# Sheet_1.net
KiCad netlist of a schematic drawn in Altium Designer
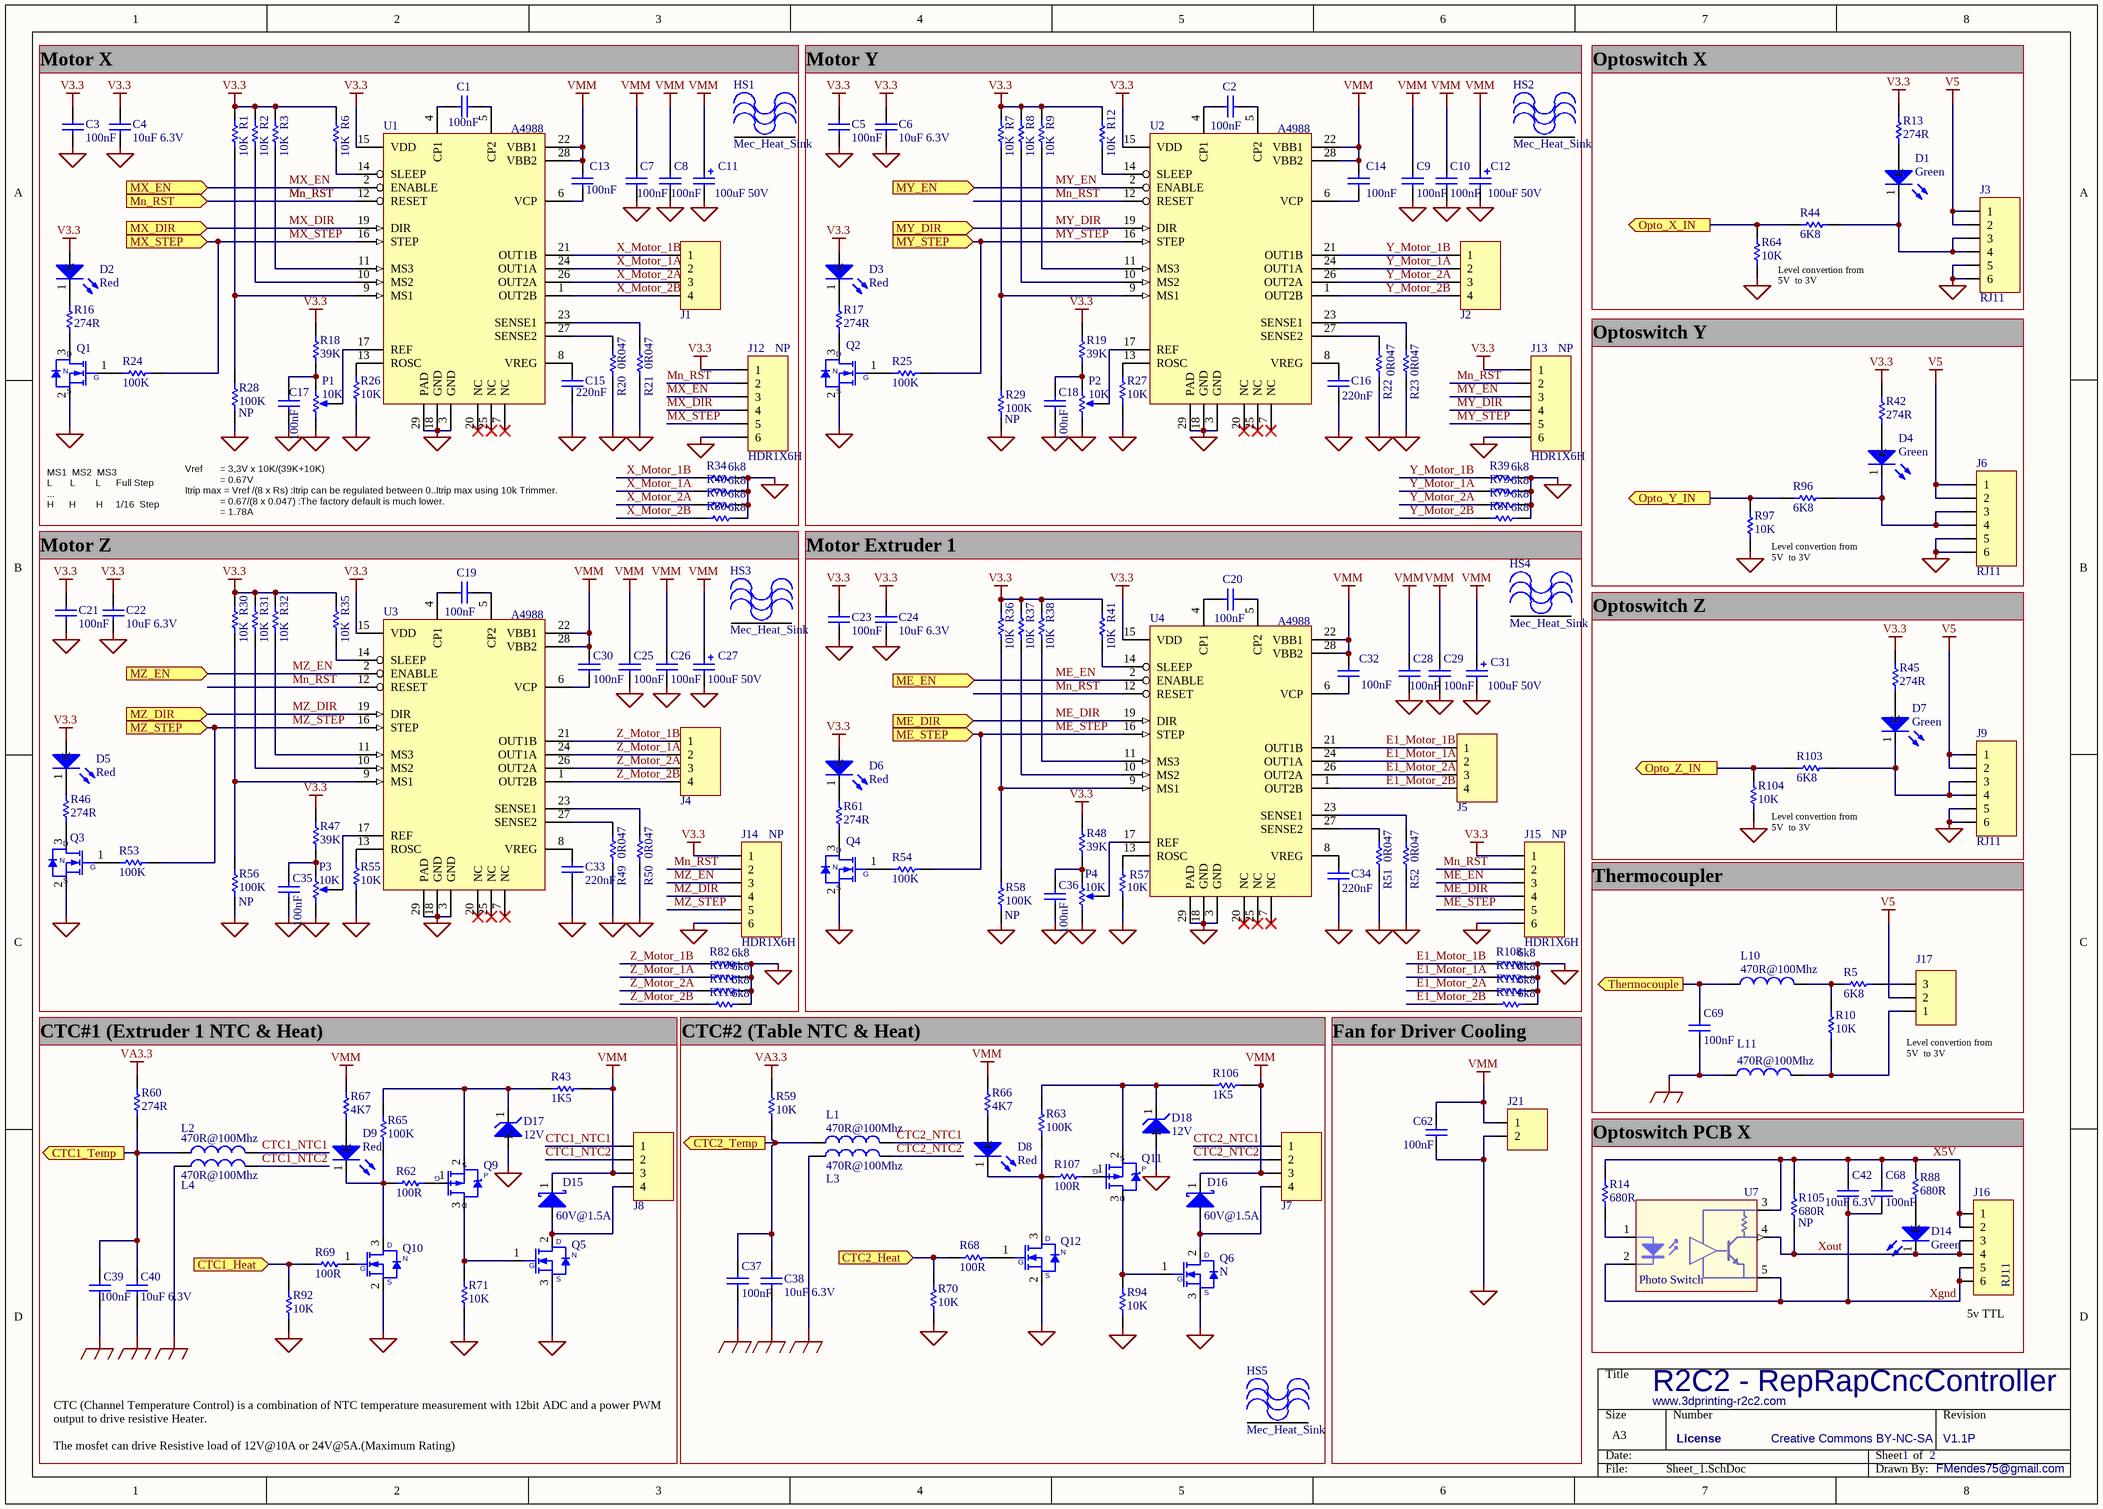
[diagram p0: Sheet_1.SchDoc]

(export (version "E")
  (design (tool "Eeschema 10.0.6"))
  (components
    (comp (ref "C1")
      (value "100nF")
      (footprint "CAPC1608M")
      (description "Capacitor - MLCC; 0603; NP0; 50V")
      (fields (field (name "PART NUMBER") "10000054") (field (name "MANUFACTURER") "Multicomp"))
      (libsource (lib "HB_DB_Components") (part "Cap Non Pol"))
    )
    (comp (ref "C2")
      (value "100nF")
      (footprint "CAPC1608M")
      (description "Capacitor Non Polarized")
      (fields (field (name "PART NUMBER") "10000054") (field (name "MANUFACTURER") "Multicomp"))
      (libsource (lib "HB_DB_Components") (part "Cap Non Pol"))
    )
    (comp (ref "C3")
      (value "100nF")
      (footprint "CAPC1608M")
      (description "Capacitor - MLCC; 0603; NP0; 50V")
      (fields (field (name "PART NUMBER") "10000054") (field (name "MANUFACTURER") "Multicomp"))
      (libsource (lib "HB_DB_Components") (part "Cap Non Pol"))
    )
    (comp (ref "C4")
      (value "10uF 6.3V")
      (footprint "CAPC2012M")
      (description "Capacitor - MLCC; 0805; Y5V; 10UF; 6.3V")
      (fields (field (name "PART NUMBER") "10000001") (field (name "MANUFACTURER") "MULTICOMP"))
      (libsource (lib "HB_DB_Components") (part "Cap Non Pol"))
    )
    (comp (ref "C5")
      (value "100nF")
      (footprint "CAPC1608M")
      (description "Capacitor - MLCC; 0603; NP0; 50V")
      (fields (field (name "PART NUMBER") "10000054") (field (name "MANUFACTURER") "Multicomp"))
      (libsource (lib "HB_DB_Components") (part "Cap Non Pol"))
    )
    (comp (ref "C6")
      (value "10uF 6.3V")
      (footprint "CAPC2012M")
      (description "Capacitor - MLCC; 0805; Y5V; 10UF; 6.3V")
      (fields (field (name "PART NUMBER") "10000001") (field (name "MANUFACTURER") "MULTICOMP"))
      (libsource (lib "HB_DB_Components") (part "Cap Non Pol"))
    )
    (comp (ref "C7")
      (value "100nF")
      (footprint "CAPC1608M")
      (description "Capacitor - MLCC; 0603; NP0; 50V")
      (fields (field (name "PART NUMBER") "10000054") (field (name "MANUFACTURER") "Multicomp"))
      (libsource (lib "HB_DB_Components") (part "Cap Non Pol"))
    )
    (comp (ref "C8")
      (value "100nF")
      (footprint "CAPC1608M")
      (description "Capacitor - MLCC; 0603; NP0; 50V")
      (fields (field (name "PART NUMBER") "10000054") (field (name "MANUFACTURER") "Multicomp"))
      (libsource (lib "HB_DB_Components") (part "Cap Non Pol"))
    )
    (comp (ref "C9")
      (value "100nF")
      (footprint "CAPC1608M")
      (description "Capacitor - MLCC; 0603; NP0; 50V")
      (fields (field (name "PART NUMBER") "10000054") (field (name "MANUFACTURER") "Multicomp"))
      (libsource (lib "HB_DB_Components") (part "Cap Non Pol"))
    )
    (comp (ref "C10")
      (value "100nF")
      (footprint "CAPC1608M")
      (description "Capacitor - MLCC; 0603; NP0; 50V")
      (fields (field (name "PART NUMBER") "10000054") (field (name "MANUFACTURER") "Multicomp"))
      (libsource (lib "HB_DB_Components") (part "Cap Non Pol"))
    )
    (comp (ref "C11")
      (value "100uF 50V")
      (footprint "CAPAE100X100M")
      (description "Capacitor - Al. Electrolytic; 100UF; 50V")
      (fields (field (name "PART NUMBER") "10000069") (field (name "MANUFACTURER") "Vishay"))
      (libsource (lib "HB_DB_Components") (part "Cap Pol"))
    )
    (comp (ref "C12")
      (value "100uF 50V")
      (footprint "CAPAE100X100M")
      (description "Capacitor - Al. Electrolytic; 100UF; 50V")
      (fields (field (name "PART NUMBER") "10000069") (field (name "MANUFACTURER") "Vishay"))
      (libsource (lib "HB_DB_Components") (part "Cap Pol"))
    )
    (comp (ref "C13")
      (value "100nF")
      (footprint "CAPC1608M")
      (description "Capacitor - MLCC; 0603; NP0; 50V")
      (fields (field (name "PART NUMBER") "10000054") (field (name "MANUFACTURER") "Multicomp"))
      (libsource (lib "HB_DB_Components") (part "Cap Non Pol"))
    )
    (comp (ref "C14")
      (value "100nF")
      (footprint "CAPC1608M")
      (description "Capacitor - MLCC; 0603; NP0; 50V")
      (fields (field (name "PART NUMBER") "10000054") (field (name "MANUFACTURER") "Multicomp"))
      (libsource (lib "HB_DB_Components") (part "Cap Non Pol"))
    )
    (comp (ref "C15")
      (value "220nF")
      (footprint "CAPC1608M")
      (description "Capacitor - MLCC; 0603; NP0; 50V")
      (fields (field (name "PART NUMBER") "10000059") (field (name "MANUFACTURER") "Multicomp"))
      (libsource (lib "HB_DB_Components") (part "Cap Non Pol"))
    )
    (comp (ref "C16")
      (value "220nF")
      (footprint "CAPC1608M")
      (description "Capacitor - MLCC; 0603; NP0; 50V")
      (fields (field (name "PART NUMBER") "10000059") (field (name "MANUFACTURER") "Multicomp"))
      (libsource (lib "HB_DB_Components") (part "Cap Non Pol"))
    )
    (comp (ref "C17")
      (value "100nF")
      (footprint "CAPC1608M")
      (description "Capacitor - MLCC; 0603; NP0; 50V")
      (fields (field (name "PART NUMBER") "10000054") (field (name "MANUFACTURER") "Multicomp"))
      (libsource (lib "HB_DB_Components") (part "Cap Non Pol"))
    )
    (comp (ref "C18")
      (value "100nF")
      (footprint "CAPC1608M")
      (description "Capacitor - MLCC; 0603; NP0; 50V")
      (fields (field (name "PART NUMBER") "10000054") (field (name "MANUFACTURER") "Multicomp"))
      (libsource (lib "HB_DB_Components") (part "Cap Non Pol"))
    )
    (comp (ref "C19")
      (value "100nF")
      (footprint "CAPC1608M")
      (description "Capacitor - MLCC; 0603; NP0; 50V")
      (fields (field (name "PART NUMBER") "10000054") (field (name "MANUFACTURER") "Multicomp"))
      (libsource (lib "HB_DB_Components") (part "Cap Non Pol"))
    )
    (comp (ref "C20")
      (value "100nF")
      (footprint "CAPC1608M")
      (description "Capacitor Non Polarized")
      (fields (field (name "PART NUMBER") "10000054") (field (name "MANUFACTURER") "Multicomp"))
      (libsource (lib "HB_DB_Components") (part "Cap Non Pol"))
    )
    (comp (ref "C21")
      (value "100nF")
      (footprint "CAPC1608M")
      (description "Capacitor - MLCC; 0603; NP0; 50V")
      (fields (field (name "PART NUMBER") "10000054") (field (name "MANUFACTURER") "Multicomp"))
      (libsource (lib "HB_DB_Components") (part "Cap Non Pol"))
    )
    (comp (ref "C22")
      (value "10uF 6.3V")
      (footprint "CAPC2012M")
      (description "Capacitor - MLCC; 0805; Y5V; 10UF; 6.3V")
      (fields (field (name "PART NUMBER") "10000001") (field (name "MANUFACTURER") "MULTICOMP"))
      (libsource (lib "HB_DB_Components") (part "Cap Non Pol"))
    )
    (comp (ref "C23")
      (value "100nF")
      (footprint "CAPC1608M")
      (description "Capacitor - MLCC; 0603; NP0; 50V")
      (fields (field (name "PART NUMBER") "10000054") (field (name "MANUFACTURER") "Multicomp"))
      (libsource (lib "HB_DB_Components") (part "Cap Non Pol"))
    )
    (comp (ref "C24")
      (value "10uF 6.3V")
      (footprint "CAPC2012M")
      (description "Capacitor - MLCC; 0805; Y5V; 10UF; 6.3V")
      (fields (field (name "PART NUMBER") "10000001") (field (name "MANUFACTURER") "MULTICOMP"))
      (libsource (lib "HB_DB_Components") (part "Cap Non Pol"))
    )
    (comp (ref "C25")
      (value "100nF")
      (footprint "CAPC1608M")
      (description "Capacitor - MLCC; 0603; NP0; 50V")
      (fields (field (name "PART NUMBER") "10000054") (field (name "MANUFACTURER") "Multicomp"))
      (libsource (lib "HB_DB_Components") (part "Cap Non Pol"))
    )
    (comp (ref "C26")
      (value "100nF")
      (footprint "CAPC1608M")
      (description "Capacitor - MLCC; 0603; NP0; 50V")
      (fields (field (name "PART NUMBER") "10000054") (field (name "MANUFACTURER") "Multicomp"))
      (libsource (lib "HB_DB_Components") (part "Cap Non Pol"))
    )
    (comp (ref "C27")
      (value "100uF 50V")
      (footprint "CAPAE100X100M")
      (description "Capacitor - Al. Electrolytic; 100UF; 50V")
      (fields (field (name "PART NUMBER") "10000069") (field (name "MANUFACTURER") "Vishay"))
      (libsource (lib "HB_DB_Components") (part "Cap Pol"))
    )
    (comp (ref "C28")
      (value "100nF")
      (footprint "CAPC1608M")
      (description "Capacitor - MLCC; 0603; NP0; 50V")
      (fields (field (name "PART NUMBER") "10000054") (field (name "MANUFACTURER") "Multicomp"))
      (libsource (lib "HB_DB_Components") (part "Cap Non Pol"))
    )
    (comp (ref "C29")
      (value "100nF")
      (footprint "CAPC1608M")
      (description "Capacitor - MLCC; 0603; NP0; 50V")
      (fields (field (name "PART NUMBER") "10000054") (field (name "MANUFACTURER") "Multicomp"))
      (libsource (lib "HB_DB_Components") (part "Cap Non Pol"))
    )
    (comp (ref "C30")
      (value "100nF")
      (footprint "CAPC1608M")
      (description "Capacitor - MLCC; 0603; NP0; 50V")
      (fields (field (name "PART NUMBER") "10000054") (field (name "MANUFACTURER") "Multicomp"))
      (libsource (lib "HB_DB_Components") (part "Cap Non Pol"))
    )
    (comp (ref "C31")
      (value "100uF 50V")
      (footprint "CAPAE100X100M")
      (description "Capacitor - Al. Electrolytic; 100UF; 50V")
      (fields (field (name "PART NUMBER") "10000069") (field (name "MANUFACTURER") "Vishay"))
      (libsource (lib "HB_DB_Components") (part "Cap Pol"))
    )
    (comp (ref "C32")
      (value "100nF")
      (footprint "CAPC1608M")
      (description "Capacitor - MLCC; 0603; NP0; 50V")
      (fields (field (name "PART NUMBER") "10000054") (field (name "MANUFACTURER") "Multicomp"))
      (libsource (lib "HB_DB_Components") (part "Cap Non Pol"))
    )
    (comp (ref "C33")
      (value "220nF")
      (footprint "CAPC1608M")
      (description "Capacitor - MLCC; 0603; NP0; 50V")
      (fields (field (name "PART NUMBER") "10000059") (field (name "MANUFACTURER") "Multicomp"))
      (libsource (lib "HB_DB_Components") (part "Cap Non Pol"))
    )
    (comp (ref "C34")
      (value "220nF")
      (footprint "CAPC1608M")
      (description "Capacitor - MLCC; 0603; NP0; 50V")
      (fields (field (name "PART NUMBER") "10000059") (field (name "MANUFACTURER") "Multicomp"))
      (libsource (lib "HB_DB_Components") (part "Cap Non Pol"))
    )
    (comp (ref "C35")
      (value "100nF")
      (footprint "CAPC1608M")
      (description "Capacitor - MLCC; 0603; NP0; 50V")
      (fields (field (name "PART NUMBER") "10000054") (field (name "MANUFACTURER") "Multicomp"))
      (libsource (lib "HB_DB_Components") (part "Cap Non Pol"))
    )
    (comp (ref "C36")
      (value "100nF")
      (footprint "CAPC1608M")
      (description "Capacitor - MLCC; 0603; NP0; 50V")
      (fields (field (name "PART NUMBER") "10000054") (field (name "MANUFACTURER") "Multicomp"))
      (libsource (lib "HB_DB_Components") (part "Cap Non Pol"))
    )
    (comp (ref "C37")
      (value "100nF")
      (footprint "CAPC1608M")
      (description "Capacitor - MLCC; 0603; NP0; 50V")
      (fields (field (name "PART NUMBER") "10000054") (field (name "MANUFACTURER") "Multicomp"))
      (libsource (lib "HB_DB_Components") (part "Cap Non Pol"))
    )
    (comp (ref "C38")
      (value "10uF 6.3V")
      (footprint "CAPC2012M")
      (description "Capacitor - MLCC; 0805; Y5V; 10UF; 6.3V")
      (fields (field (name "PART NUMBER") "10000001") (field (name "MANUFACTURER") "MULTICOMP"))
      (libsource (lib "HB_DB_Components") (part "Cap Non Pol"))
    )
    (comp (ref "C39")
      (value "100nF")
      (footprint "CAPC1608M")
      (description "Capacitor - MLCC; 0603; NP0; 50V")
      (fields (field (name "PART NUMBER") "10000054") (field (name "MANUFACTURER") "Multicomp"))
      (libsource (lib "HB_DB_Components") (part "Cap Non Pol"))
    )
    (comp (ref "C40")
      (value "10uF 6.3V")
      (footprint "CAPC2012M")
      (description "Capacitor - MLCC; 0805; Y5V; 10UF; 6.3V")
      (fields (field (name "PART NUMBER") "10000001") (field (name "MANUFACTURER") "MULTICOMP"))
      (libsource (lib "HB_DB_Components") (part "Cap Non Pol"))
    )
    (comp (ref "C42")
      (value "10uF 6.3V")
      (footprint "CAPC2012M")
      (description "Capacitor - MLCC; 0805; Y5V; 10UF; 6.3V")
      (fields (field (name "PART NUMBER") "10000001") (field (name "MANUFACTURER") "MULTICOMP"))
      (libsource (lib "HB_DB_Components") (part "Cap Non Pol"))
    )
    (comp (ref "C62")
      (value "100nF")
      (footprint "CAPC1608M")
      (description "Capacitor - MLCC; 0603; NP0; 50V")
      (fields (field (name "PART NUMBER") "10000054") (field (name "MANUFACTURER") "Multicomp"))
      (libsource (lib "HB_DB_Components") (part "Cap Non Pol"))
    )
    (comp (ref "C68")
      (value "100nF")
      (footprint "CAPC1608M")
      (description "Capacitor - MLCC; 0603; NP0; 50V")
      (fields (field (name "PART NUMBER") "10000054") (field (name "MANUFACTURER") "Multicomp"))
      (libsource (lib "HB_DB_Components") (part "Cap Non Pol"))
    )
    (comp (ref "C69")
      (value "100nF")
      (footprint "CAPC1608M")
      (description "Capacitor - MLCC; 0603; NP0; 50V")
      (fields (field (name "PART NUMBER") "10000054") (field (name "MANUFACTURER") "Multicomp"))
      (libsource (lib "HB_DB_Components") (part "Cap Non Pol"))
    )
    (comp (ref "D1")
      (value "Green")
      (footprint "LEDM_3216X12M")
      (description "Led - 1206; Green OSRAM")
      (fields (field (name "PART NUMBER") "10000008") (field (name "MANUFACTURER") "OSRAM"))
      (libsource (lib "HB_DB_Components") (part "LED"))
    )
    (comp (ref "D2")
      (value "Red")
      (footprint "LEDM_3216X12M")
      (description "Led - 1206; Red")
      (fields (field (name "PART NUMBER") "10000089"))
      (libsource (lib "HB_DB_Components") (part "LED"))
    )
    (comp (ref "D3")
      (value "Red")
      (footprint "LEDM_3216X12M")
      (description "Led - 1206; Red")
      (fields (field (name "PART NUMBER") "10000089"))
      (libsource (lib "HB_DB_Components") (part "LED"))
    )
    (comp (ref "D4")
      (value "Green")
      (footprint "LEDM_3216X12M")
      (description "Led - 1206; Green OSRAM")
      (fields (field (name "PART NUMBER") "10000008") (field (name "MANUFACTURER") "OSRAM"))
      (libsource (lib "HB_DB_Components") (part "LED"))
    )
    (comp (ref "D5")
      (value "Red")
      (footprint "LEDM_3216X12M")
      (description "Led - 1206; Red")
      (fields (field (name "PART NUMBER") "10000089"))
      (libsource (lib "HB_DB_Components") (part "LED"))
    )
    (comp (ref "D6")
      (value "Red")
      (footprint "LEDM_3216X12M")
      (description "Led - 1206; Red")
      (fields (field (name "PART NUMBER") "10000089"))
      (libsource (lib "HB_DB_Components") (part "LED"))
    )
    (comp (ref "D7")
      (value "Green")
      (footprint "LEDM_3216X12M")
      (description "Led - 1206; Green OSRAM")
      (fields (field (name "PART NUMBER") "10000008") (field (name "MANUFACTURER") "OSRAM"))
      (libsource (lib "HB_DB_Components") (part "LED"))
    )
    (comp (ref "D8")
      (value "Red")
      (footprint "LEDM_3216X12M")
      (description "Led - 1206; Red")
      (fields (field (name "PART NUMBER") "10000089"))
      (libsource (lib "HB_DB_Components") (part "LED"))
    )
    (comp (ref "D9")
      (value "Red")
      (footprint "LEDM_3216X12M")
      (description "Led - 1206; Red")
      (fields (field (name "PART NUMBER") "10000089"))
      (libsource (lib "HB_DB_Components") (part "LED"))
    )
    (comp (ref "D14")
      (value "Green")
      (footprint "LEDM_3216X12M")
      (description "Led - 1206; Green OSRAM")
      (fields (field (name "PART NUMBER") "10000008") (field (name "MANUFACTURER") "OSRAM"))
      (libsource (lib "HB_DB_Components") (part "LED"))
    )
    (comp (ref "D15")
      (value "60V@1.5A")
      (footprint "SMA")
      (description "Diode - Schottky; 1.5A; 60V")
      (fields (field (name "PART NUMBER") "10000010") (field (name "MANUFACTURER") "VISHAY"))
      (libsource (lib "HB_DB_Components") (part "D Schottky"))
    )
    (comp (ref "D16")
      (value "60V@1.5A")
      (footprint "SMA")
      (description "Diode - Schottky; 1.5A; 60V")
      (fields (field (name "PART NUMBER") "10000010") (field (name "MANUFACTURER") "VISHAY"))
      (libsource (lib "HB_DB_Components") (part "D Schottky"))
    )
    (comp (ref "D17")
      (value "12V")
      (footprint "SOD323")
      (description "Diode - Zener; 0.4W; 12V")
      (fields (field (name "PART NUMBER") "10000088") (field (name "MANUFACTURER") "NXP"))
      (libsource (lib "HB_DB_Components") (part "D Zener"))
    )
    (comp (ref "D18")
      (value "12V")
      (footprint "SOD323")
      (description "Diode - Zener; 0.4W; 12V")
      (fields (field (name "PART NUMBER") "10000088") (field (name "MANUFACTURER") "NXP"))
      (libsource (lib "HB_DB_Components") (part "D Zener"))
    )
    (comp (ref "HS1")
      (value "Mec_Heat_Sink")
      (footprint "HS_180x130x50")
      (description "Heat Sink - IC stiker")
      (fields (field (name "PART NUMBER") "10000090"))
      (libsource (lib "HB_DB_Components") (part "Mec_Heat_Sink"))
    )
    (comp (ref "HS2")
      (value "Mec_Heat_Sink")
      (footprint "HS_180x130x50")
      (description "Heat Sink - IC stiker")
      (fields (field (name "PART NUMBER") "10000090"))
      (libsource (lib "HB_DB_Components") (part "Mec_Heat_Sink"))
    )
    (comp (ref "HS3")
      (value "Mec_Heat_Sink")
      (footprint "HS_180x130x50")
      (description "Heat Sink - IC stiker")
      (fields (field (name "PART NUMBER") "10000090"))
      (libsource (lib "HB_DB_Components") (part "Mec_Heat_Sink"))
    )
    (comp (ref "HS4")
      (value "Mec_Heat_Sink")
      (footprint "HS_180x130x50")
      (description "Heat Sink - IC stiker")
      (fields (field (name "PART NUMBER") "10000090"))
      (libsource (lib "HB_DB_Components") (part "Mec_Heat_Sink"))
    )
    (comp (ref "HS5")
      (value "Mec_Heat_Sink")
      (footprint "FK_244_13_D2PAK")
      (description "Heat Sink - For D2PAK")
      (fields (field (name "PART NUMBER") "10000091") (field (name "MANUFACTURER") "Fischer Elektronik"))
      (libsource (lib "HB_DB_Components") (part "Mec_Heat_Sink"))
    )
    (comp (ref "J1")
      (value "Con 4")
      (footprint "WEIDMULLER_SL-5.08-04-90B")
      (description "Connector - Header male; Screw; 4way; Hor.")
      (fields (field (name "PART NUMBER") "10000023") (field (name "MANUFACTURER") "WEIDMULLER"))
      (libsource (lib "HB_DB_Components") (part "Con 4"))
    )
    (comp (ref "J2")
      (value "Con 4")
      (footprint "WEIDMULLER_SL-5.08-04-90B")
      (description "Connector - Header male; Screw; 4way; Hor.")
      (fields (field (name "PART NUMBER") "10000023") (field (name "MANUFACTURER") "WEIDMULLER"))
      (libsource (lib "HB_DB_Components") (part "Con 4"))
    )
    (comp (ref "J3")
      (value "RJ11")
      (footprint "MOLEX_95022-2667")
      (description "Connector - PCB; RJ11; 6/4 Low Profile; Hor.")
      (fields (field (name "PART NUMBER") "10000062") (field (name "MANUFACTURER") "Molex"))
      (libsource (lib "HB_DB_Components") (part "Con 6"))
    )
    (comp (ref "J4")
      (value "Con 4")
      (footprint "WEIDMULLER_SL-5.08-04-90B")
      (description "Connector - Header male; Screw; 4way; Hor.")
      (fields (field (name "PART NUMBER") "10000023") (field (name "MANUFACTURER") "WEIDMULLER"))
      (libsource (lib "HB_DB_Components") (part "Con 4"))
    )
    (comp (ref "J5")
      (value "Con 4")
      (footprint "WEIDMULLER_SL-5.08-04-90B")
      (description "Connector - Header male; Screw; 4way; Hor.")
      (fields (field (name "PART NUMBER") "10000023") (field (name "MANUFACTURER") "WEIDMULLER"))
      (libsource (lib "HB_DB_Components") (part "Con 4"))
    )
    (comp (ref "J6")
      (value "RJ11")
      (footprint "MOLEX_95022-2667")
      (description "Connector - PCB; RJ11; 6/4 Low Profile; Hor.")
      (fields (field (name "PART NUMBER") "10000062") (field (name "MANUFACTURER") "Molex"))
      (libsource (lib "HB_DB_Components") (part "Con 6"))
    )
    (comp (ref "J7")
      (value "Con 4")
      (footprint "WEIDMULLER_SL-5.08-04-90B")
      (description "Connector - Header male; Screw; 4way; Hor.")
      (fields (field (name "PART NUMBER") "10000023") (field (name "MANUFACTURER") "WEIDMULLER"))
      (libsource (lib "HB_DB_Components") (part "Con 4"))
    )
    (comp (ref "J8")
      (value "Con 4")
      (footprint "WEIDMULLER_SL-5.08-04-90B")
      (description "Connector - Header male; Screw; 4way; Hor.")
      (fields (field (name "PART NUMBER") "10000023") (field (name "MANUFACTURER") "WEIDMULLER"))
      (libsource (lib "HB_DB_Components") (part "Con 4"))
    )
    (comp (ref "J9")
      (value "RJ11")
      (footprint "MOLEX_95022-2667")
      (description "Connector - PCB; RJ11; 6/4 Low Profile; Hor.")
      (fields (field (name "PART NUMBER") "10000062") (field (name "MANUFACTURER") "Molex"))
      (libsource (lib "HB_DB_Components") (part "Con 6"))
    )
    (comp (ref "J12")
      (value "HDR1X6H")
      (footprint "HDR1X6")
      (description "Connector - Header 1x6; Vert..")
      (fields (field (name "PART NUMBER") "10000093") (field (name "POPULATE") "NP"))
      (libsource (lib "HB_DB_Components") (part "Con 6"))
    )
    (comp (ref "J13")
      (value "HDR1X6H")
      (footprint "HDR1X6")
      (description "Connector - Header 1x6; Vert..")
      (fields (field (name "PART NUMBER") "10000093") (field (name "POPULATE") "NP"))
      (libsource (lib "HB_DB_Components") (part "Con 6"))
    )
    (comp (ref "J14")
      (value "HDR1X6H")
      (footprint "HDR1X6")
      (description "Connector - Header 1x6; Vert..")
      (fields (field (name "PART NUMBER") "10000093") (field (name "POPULATE") "NP"))
      (libsource (lib "HB_DB_Components") (part "Con 6"))
    )
    (comp (ref "J15")
      (value "HDR1X6H")
      (footprint "HDR1X6")
      (description "Connector - Header 1x6; Vert..")
      (fields (field (name "PART NUMBER") "10000093") (field (name "POPULATE") "NP"))
      (libsource (lib "HB_DB_Components") (part "Con 6"))
    )
    (comp (ref "J16")
      (value "RJ11")
      (footprint "MOLEX_95022-2667")
      (description "Connector - PCB; RJ11; 6/4 Low Profile; Hor.")
      (fields (field (name "PART NUMBER") "10000062") (field (name "MANUFACTURER") "Molex"))
      (libsource (lib "HB_DB_Components") (part "Con 6"))
    )
    (comp (ref "J17")
      (value "Con 3")
      (footprint "phoenix-contact_smkdsn-5.08")
      (description "Terminal Block")
      (fields (field (name "PART NUMBER") "10000095") (field (name "MANUFACTURER") "Phoenix_Contact"))
      (libsource (lib "HB_DB_Components") (part "Con 3"))
    )
    (comp (ref "J21")
      (value "Con 2")
      (footprint "MOLEX_22-29-2021")
      (description "Connector - PCB; Header; SQ Pin, 2 way; 2.54mm; Vert")
      (fields (field (name "PART NUMBER") "10000097") (field (name "MANUFACTURER") "Molex"))
      (libsource (lib "HB_DB_Components") (part "Con 2"))
    )
    (comp (ref "L1")
      (value "470R@100Mhz")
      (footprint "INDC1608M")
      (description "Ferrite Bead - 470OHM; 0603")
      (fields (field (name "PART NUMBER") "10000032") (field (name "MANUFACTURER") "MURATA"))
      (libsource (lib "HB_DB_Components") (part "Ind"))
    )
    (comp (ref "L2")
      (value "470R@100Mhz")
      (footprint "INDC1608M")
      (description "Ferrite Bead - 470OHM; 0603")
      (fields (field (name "PART NUMBER") "10000032") (field (name "MANUFACTURER") "MURATA"))
      (libsource (lib "HB_DB_Components") (part "Ind"))
    )
    (comp (ref "L3")
      (value "470R@100Mhz")
      (footprint "INDC1608M")
      (description "Ferrite Bead - 470OHM; 0603")
      (fields (field (name "PART NUMBER") "10000032") (field (name "MANUFACTURER") "MURATA"))
      (libsource (lib "HB_DB_Components") (part "Ind"))
    )
    (comp (ref "L4")
      (value "470R@100Mhz")
      (footprint "INDC1608M")
      (description "Ferrite Bead - 470OHM; 0603")
      (fields (field (name "PART NUMBER") "10000032") (field (name "MANUFACTURER") "MURATA"))
      (libsource (lib "HB_DB_Components") (part "Ind"))
    )
    (comp (ref "L10")
      (value "470R@100Mhz")
      (footprint "INDC1608M")
      (description "Ferrite Bead - 470OHM; 0603")
      (fields (field (name "PART NUMBER") "10000032") (field (name "MANUFACTURER") "MURATA"))
      (libsource (lib "HB_DB_Components") (part "Ind"))
    )
    (comp (ref "L11")
      (value "470R@100Mhz")
      (footprint "INDC1608M")
      (description "Ferrite Bead - 470OHM; 0603")
      (fields (field (name "PART NUMBER") "10000032") (field (name "MANUFACTURER") "MURATA"))
      (libsource (lib "HB_DB_Components") (part "Ind"))
    )
    (comp (ref "P1")
      (value "10K")
      (footprint "Trimmer_14")
      (description "Resistor - Trimmer; 1/4\"; 10K")
      (fields (field (name "PART NUMBER") "10000092") (field (name "MANUFACTURER") "Bourns"))
      (libsource (lib "HB_DB_Components") (part "Res Pot"))
    )
    (comp (ref "P2")
      (value "10K")
      (footprint "Trimmer_14")
      (description "Resistor - Trimmer; 1/4\"; 10K")
      (fields (field (name "PART NUMBER") "10000092") (field (name "MANUFACTURER") "Bourns"))
      (libsource (lib "HB_DB_Components") (part "Res Pot"))
    )
    (comp (ref "P3")
      (value "10K")
      (footprint "Trimmer_14")
      (description "Resistor - Trimmer; 1/4\"; 10K")
      (fields (field (name "PART NUMBER") "10000092") (field (name "MANUFACTURER") "Bourns"))
      (libsource (lib "HB_DB_Components") (part "Res Pot"))
    )
    (comp (ref "P4")
      (value "10K")
      (footprint "Trimmer_14")
      (description "Resistor - Trimmer; 1/4\"; 10K")
      (fields (field (name "PART NUMBER") "10000092") (field (name "MANUFACTURER") "Bourns"))
      (libsource (lib "HB_DB_Components") (part "Res Pot"))
    )
    (comp (ref "Q1")
      (value "N")
      (footprint "SOT323-3AM")
      (description "Mosfet - N; 60V; 0.3A;")
      (fields (field (name "PART NUMBER") "10000039") (field (name "MANUFACTURER") "NXP"))
      (libsource (lib "HB_DB_Components") (part "Q MOSFET-N"))
    )
    (comp (ref "Q2")
      (value "N")
      (footprint "SOT323-3AM")
      (description "Mosfet - N; 60V; 0.3A;")
      (fields (field (name "PART NUMBER") "10000039") (field (name "MANUFACTURER") "NXP"))
      (libsource (lib "HB_DB_Components") (part "Q MOSFET-N"))
    )
    (comp (ref "Q3")
      (value "N")
      (footprint "SOT323-3AM")
      (description "Mosfet - N; 60V; 0.3A;")
      (fields (field (name "PART NUMBER") "10000039") (field (name "MANUFACTURER") "NXP"))
      (libsource (lib "HB_DB_Components") (part "Q MOSFET-N"))
    )
    (comp (ref "Q4")
      (value "N")
      (footprint "SOT323-3AM")
      (description "Mosfet - N; 60V; 0.3A;")
      (fields (field (name "PART NUMBER") "10000039") (field (name "MANUFACTURER") "NXP"))
      (libsource (lib "HB_DB_Components") (part "Q MOSFET-N"))
    )
    (comp (ref "Q5")
      (value "N")
      (footprint "D2PAK")
      (description "N-channel Enhancement Mode Field-effect Transistor (123/gds)")
      (fields (field (name "PART NUMBER") "10000078") (field (name "MANUFACTURER") "IR"))
      (libsource (lib "HB_DB_Components") (part "Q MOSFET-N_gds"))
    )
    (comp (ref "Q6")
      (value "N")
      (footprint "D2PAK")
      (description "N-channel Enhancement Mode Field-effect Transistor (123/gds)")
      (fields (field (name "PART NUMBER") "10000078") (field (name "MANUFACTURER") "IR"))
      (libsource (lib "HB_DB_Components") (part "Q MOSFET-N_gds"))
    )
    (comp (ref "Q9")
      (value "P")
      (footprint "SOT23-3M")
      (description "Mosfet - Power; Vdss=-30v; Rds=0.60; Id=-0.6A")
      (fields (field (name "PART NUMBER") "10000076") (field (name "MANUFACTURER") "IR"))
      (libsource (lib "HB_DB_Components") (part "MOS-P"))
    )
    (comp (ref "Q10")
      (value "N")
      (footprint "SOT323-3AM")
      (description "Mosfet - N; 60V; 0.3A;")
      (fields (field (name "PART NUMBER") "10000039") (field (name "MANUFACTURER") "NXP"))
      (libsource (lib "HB_DB_Components") (part "Q MOSFET-N"))
    )
    (comp (ref "Q11")
      (value "P")
      (footprint "SOT23-3M")
      (description "Mosfet - Power; Vdss=-30v; Rds=0.60; Id=-0.6A")
      (fields (field (name "PART NUMBER") "10000076") (field (name "MANUFACTURER") "IR"))
      (libsource (lib "HB_DB_Components") (part "MOS-P"))
    )
    (comp (ref "Q12")
      (value "N")
      (footprint "SOT323-3AM")
      (description "Mosfet - N; 60V; 0.3A;")
      (fields (field (name "PART NUMBER") "10000039") (field (name "MANUFACTURER") "NXP"))
      (libsource (lib "HB_DB_Components") (part "Q MOSFET-N"))
    )
    (comp (ref "R1")
      (value "10K")
      (footprint "RESC1608M")
      (description "Resistor - 0603; 0.063W; 1%")
      (fields (field (name "PART NUMBER") "10000044") (field (name "MANUFACTURER") "Multicomp"))
      (libsource (lib "HB_DB_Components") (part "Res"))
    )
    (comp (ref "R2")
      (value "10K")
      (footprint "RESC1608M")
      (description "Resistor - 0603; 0.063W; 1%")
      (fields (field (name "PART NUMBER") "10000044") (field (name "MANUFACTURER") "Multicomp"))
      (libsource (lib "HB_DB_Components") (part "Res"))
    )
    (comp (ref "R3")
      (value "10K")
      (footprint "RESC1608M")
      (description "Resistor - 0603; 0.063W; 1%")
      (fields (field (name "PART NUMBER") "10000044") (field (name "MANUFACTURER") "Multicomp"))
      (libsource (lib "HB_DB_Components") (part "Res"))
    )
    (comp (ref "R5")
      (value "6K8")
      (footprint "RESC1608M")
      (description "Resistor - 0603; 0.063W; 1%")
      (fields (field (name "PART NUMBER") "10000096"))
      (libsource (lib "HB_DB_Components") (part "Res"))
    )
    (comp (ref "R6")
      (value "10K")
      (footprint "RESC1608M")
      (description "Resistor - 0603; 0.063W; 1%")
      (fields (field (name "PART NUMBER") "10000044") (field (name "MANUFACTURER") "Multicomp"))
      (libsource (lib "HB_DB_Components") (part "Res"))
    )
    (comp (ref "R7")
      (value "10K")
      (footprint "RESC1608M")
      (description "Resistor - 0603; 0.063W; 1%")
      (fields (field (name "PART NUMBER") "10000044") (field (name "MANUFACTURER") "Multicomp"))
      (libsource (lib "HB_DB_Components") (part "Res"))
    )
    (comp (ref "R8")
      (value "10K")
      (footprint "RESC1608M")
      (description "Resistor - 0603; 0.063W; 1%")
      (fields (field (name "PART NUMBER") "10000044") (field (name "MANUFACTURER") "Multicomp"))
      (libsource (lib "HB_DB_Components") (part "Res"))
    )
    (comp (ref "R9")
      (value "10K")
      (footprint "RESC1608M")
      (description "Resistor - 0603; 0.063W; 1%")
      (fields (field (name "PART NUMBER") "10000044") (field (name "MANUFACTURER") "Multicomp"))
      (libsource (lib "HB_DB_Components") (part "Res"))
    )
    (comp (ref "R10")
      (value "10K")
      (footprint "RESC1608M")
      (description "Resistor")
      (fields (field (name "PART NUMBER") "10000044") (field (name "MANUFACTURER") "Multicomp"))
      (libsource (lib "HB_DB_Components") (part "Res"))
    )
    (comp (ref "R12")
      (value "10K")
      (footprint "RESC1608M")
      (description "Resistor - 0603; 0.063W; 1%")
      (fields (field (name "PART NUMBER") "10000044") (field (name "MANUFACTURER") "Multicomp"))
      (libsource (lib "HB_DB_Components") (part "Res"))
    )
    (comp (ref "R13")
      (value "274R")
      (footprint "RESC1608M")
      (description "Resistor - 0603; 0.063W; 1%")
      (fields (field (name "PART NUMBER") "10000041") (field (name "MANUFACTURER") "Multicomp"))
      (libsource (lib "HB_DB_Components") (part "Res"))
    )
    (comp (ref "R14")
      (value "680R")
      (footprint "RESC1608M")
      (description "Resistor - 0603; 0.063W; 1%")
      (fields (field (name "PART NUMBER") "10000061") (field (name "MANUFACTURER") "Multicomp"))
      (libsource (lib "HB_DB_Components") (part "Res"))
    )
    (comp (ref "R16")
      (value "274R")
      (footprint "RESC1608M")
      (description "Resistor - 0603; 0.063W; 1%")
      (fields (field (name "PART NUMBER") "10000041") (field (name "MANUFACTURER") "Multicomp"))
      (libsource (lib "HB_DB_Components") (part "Res"))
    )
    (comp (ref "R17")
      (value "274R")
      (footprint "RESC1608M")
      (description "Resistor - 0603; 0.063W; 1%")
      (fields (field (name "PART NUMBER") "10000041") (field (name "MANUFACTURER") "Multicomp"))
      (libsource (lib "HB_DB_Components") (part "Res"))
    )
    (comp (ref "R18")
      (value "39K")
      (footprint "RESC1608M")
      (description "Resistor - 0603; 0.063W; 1%")
      (fields (field (name "PART NUMBER") "10000087"))
      (libsource (lib "HB_DB_Components") (part "Res"))
    )
    (comp (ref "R19")
      (value "39K")
      (footprint "RESC1608M")
      (description "Resistor - 0603; 0.063W; 1%")
      (fields (field (name "PART NUMBER") "10000087"))
      (libsource (lib "HB_DB_Components") (part "Res"))
    )
    (comp (ref "R20")
      (value "0R047")
      (footprint "RESC3216M")
      (description "Resistor - 1206; 0.5W; 1%")
      (fields (field (name "PART NUMBER") "10000047") (field (name "MANUFACTURER") "YAGEO"))
      (libsource (lib "HB_DB_Components") (part "Res"))
    )
    (comp (ref "R21")
      (value "0R047")
      (footprint "RESC3216M")
      (description "Resistor - 1206; 0.5W; 1%")
      (fields (field (name "PART NUMBER") "10000047") (field (name "MANUFACTURER") "YAGEO"))
      (libsource (lib "HB_DB_Components") (part "Res"))
    )
    (comp (ref "R22")
      (value "0R047")
      (footprint "RESC3216M")
      (description "Resistor - 1206; 0.5W; 1%")
      (fields (field (name "PART NUMBER") "10000047") (field (name "MANUFACTURER") "YAGEO"))
      (libsource (lib "HB_DB_Components") (part "Res"))
    )
    (comp (ref "R23")
      (value "0R047")
      (footprint "RESC3216M")
      (description "Resistor - 1206; 0.5W; 1%")
      (fields (field (name "PART NUMBER") "10000047") (field (name "MANUFACTURER") "YAGEO"))
      (libsource (lib "HB_DB_Components") (part "Res"))
    )
    (comp (ref "R24")
      (value "100K")
      (footprint "RESC1608M")
      (description "Resistor - 0603; 0.063W; 1%")
      (fields (field (name "PART NUMBER") "10000045") (field (name "MANUFACTURER") "Multicomp"))
      (libsource (lib "HB_DB_Components") (part "Res"))
    )
    (comp (ref "R25")
      (value "100K")
      (footprint "RESC1608M")
      (description "Resistor - 0603; 0.063W; 1%")
      (fields (field (name "PART NUMBER") "10000045") (field (name "MANUFACTURER") "Multicomp"))
      (libsource (lib "HB_DB_Components") (part "Res"))
    )
    (comp (ref "R26")
      (value "10K")
      (footprint "RESC1608M")
      (description "Resistor - 0603; 0.063W; 1%")
      (fields (field (name "PART NUMBER") "10000044") (field (name "MANUFACTURER") "Multicomp"))
      (libsource (lib "HB_DB_Components") (part "Res"))
    )
    (comp (ref "R27")
      (value "10K")
      (footprint "RESC1608M")
      (description "Resistor - 0603; 0.063W; 1%")
      (fields (field (name "PART NUMBER") "10000044") (field (name "MANUFACTURER") "Multicomp"))
      (libsource (lib "HB_DB_Components") (part "Res"))
    )
    (comp (ref "R28")
      (value "100K")
      (footprint "RESC1608M")
      (description "Resistor - 0603; 0.063W; 1%")
      (fields
        (field (name "PART NUMBER") "10000045")
        (field (name "MANUFACTURER") "Multicomp")
        (field (name "POPULATE") "NP")
      )
      (libsource (lib "HB_DB_Components") (part "Res"))
    )
    (comp (ref "R29")
      (value "100K")
      (footprint "RESC1608M")
      (description "Resistor - 0603; 0.063W; 1%")
      (fields
        (field (name "PART NUMBER") "10000045")
        (field (name "MANUFACTURER") "Multicomp")
        (field (name "POPULATE") "NP")
      )
      (libsource (lib "HB_DB_Components") (part "Res"))
    )
    (comp (ref "R30")
      (value "10K")
      (footprint "RESC1608M")
      (description "Resistor - 0603; 0.063W; 1%")
      (fields (field (name "PART NUMBER") "10000044") (field (name "MANUFACTURER") "Multicomp"))
      (libsource (lib "HB_DB_Components") (part "Res"))
    )
    (comp (ref "R31")
      (value "10K")
      (footprint "RESC1608M")
      (description "Resistor - 0603; 0.063W; 1%")
      (fields (field (name "PART NUMBER") "10000044") (field (name "MANUFACTURER") "Multicomp"))
      (libsource (lib "HB_DB_Components") (part "Res"))
    )
    (comp (ref "R32")
      (value "10K")
      (footprint "RESC1608M")
      (description "Resistor - 0603; 0.063W; 1%")
      (fields (field (name "PART NUMBER") "10000044") (field (name "MANUFACTURER") "Multicomp"))
      (libsource (lib "HB_DB_Components") (part "Res"))
    )
    (comp (ref "R34")
      (value "6k8")
      (footprint "RESC2012L")
      (description "Resistor - 0805; 0.100W; 5%")
      (fields (field (name "PART NUMBER") "10000098"))
      (libsource (lib "HB_DB_Components") (part "Res"))
    )
    (comp (ref "R35")
      (value "10K")
      (footprint "RESC1608M")
      (description "Resistor - 0603; 0.063W; 1%")
      (fields (field (name "PART NUMBER") "10000044") (field (name "MANUFACTURER") "Multicomp"))
      (libsource (lib "HB_DB_Components") (part "Res"))
    )
    (comp (ref "R36")
      (value "10K")
      (footprint "RESC1608M")
      (description "Resistor - 0603; 0.063W; 1%")
      (fields (field (name "PART NUMBER") "10000044") (field (name "MANUFACTURER") "Multicomp"))
      (libsource (lib "HB_DB_Components") (part "Res"))
    )
    (comp (ref "R37")
      (value "10K")
      (footprint "RESC1608M")
      (description "Resistor - 0603; 0.063W; 1%")
      (fields (field (name "PART NUMBER") "10000044") (field (name "MANUFACTURER") "Multicomp"))
      (libsource (lib "HB_DB_Components") (part "Res"))
    )
    (comp (ref "R38")
      (value "10K")
      (footprint "RESC1608M")
      (description "Resistor - 0603; 0.063W; 1%")
      (fields (field (name "PART NUMBER") "10000044") (field (name "MANUFACTURER") "Multicomp"))
      (libsource (lib "HB_DB_Components") (part "Res"))
    )
    (comp (ref "R39")
      (value "6k8")
      (footprint "RESC2012L")
      (description "Resistor - 0805; 0.100W; 5%")
      (fields (field (name "PART NUMBER") "10000098"))
      (libsource (lib "HB_DB_Components") (part "Res"))
    )
    (comp (ref "R40")
      (value "6k8")
      (footprint "RESC2012L")
      (description "Resistor - 0805; 0.100W; 5%")
      (fields (field (name "PART NUMBER") "10000098"))
      (libsource (lib "HB_DB_Components") (part "Res"))
    )
    (comp (ref "R41")
      (value "10K")
      (footprint "RESC1608M")
      (description "Resistor - 0603; 0.063W; 1%")
      (fields (field (name "PART NUMBER") "10000044") (field (name "MANUFACTURER") "Multicomp"))
      (libsource (lib "HB_DB_Components") (part "Res"))
    )
    (comp (ref "R42")
      (value "274R")
      (footprint "RESC1608M")
      (description "Resistor - 0603; 0.063W; 1%")
      (fields (field (name "PART NUMBER") "10000041") (field (name "MANUFACTURER") "Multicomp"))
      (libsource (lib "HB_DB_Components") (part "Res"))
    )
    (comp (ref "R43")
      (value "1K5")
      (footprint "RESC1608M")
      (description "Resistor - 0603; 0.063W; 1%")
      (fields (field (name "PART NUMBER") "10000048") (field (name "MANUFACTURER") "Multicomp"))
      (libsource (lib "HB_DB_Components") (part "Res"))
    )
    (comp (ref "R44")
      (value "6K8")
      (footprint "RESC1608M")
      (description "Resistor - 0603; 0.063W; 1%")
      (fields (field (name "PART NUMBER") "10000096"))
      (libsource (lib "HB_DB_Components") (part "Res"))
    )
    (comp (ref "R45")
      (value "274R")
      (footprint "RESC1608M")
      (description "Resistor - 0603; 0.063W; 1%")
      (fields (field (name "PART NUMBER") "10000041") (field (name "MANUFACTURER") "Multicomp"))
      (libsource (lib "HB_DB_Components") (part "Res"))
    )
    (comp (ref "R46")
      (value "274R")
      (footprint "RESC1608M")
      (description "Resistor - 0603; 0.063W; 1%")
      (fields (field (name "PART NUMBER") "10000041") (field (name "MANUFACTURER") "Multicomp"))
      (libsource (lib "HB_DB_Components") (part "Res"))
    )
    (comp (ref "R47")
      (value "39K")
      (footprint "RESC1608M")
      (description "Resistor - 0603; 0.063W; 1%")
      (fields (field (name "PART NUMBER") "10000087"))
      (libsource (lib "HB_DB_Components") (part "Res"))
    )
    (comp (ref "R48")
      (value "39K")
      (footprint "RESC1608M")
      (description "Resistor - 0603; 0.063W; 1%")
      (fields (field (name "PART NUMBER") "10000087"))
      (libsource (lib "HB_DB_Components") (part "Res"))
    )
    (comp (ref "R49")
      (value "0R047")
      (footprint "RESC3216M")
      (description "Resistor - 1206; 0.5W; 1%")
      (fields (field (name "PART NUMBER") "10000047") (field (name "MANUFACTURER") "YAGEO"))
      (libsource (lib "HB_DB_Components") (part "Res"))
    )
    (comp (ref "R50")
      (value "0R047")
      (footprint "RESC3216M")
      (description "Resistor - 1206; 0.5W; 1%")
      (fields (field (name "PART NUMBER") "10000047") (field (name "MANUFACTURER") "YAGEO"))
      (libsource (lib "HB_DB_Components") (part "Res"))
    )
    (comp (ref "R51")
      (value "0R047")
      (footprint "RESC3216M")
      (description "Resistor - 1206; 0.5W; 1%")
      (fields (field (name "PART NUMBER") "10000047") (field (name "MANUFACTURER") "YAGEO"))
      (libsource (lib "HB_DB_Components") (part "Res"))
    )
    (comp (ref "R52")
      (value "0R047")
      (footprint "RESC3216M")
      (description "Resistor - 1206; 0.5W; 1%")
      (fields (field (name "PART NUMBER") "10000047") (field (name "MANUFACTURER") "YAGEO"))
      (libsource (lib "HB_DB_Components") (part "Res"))
    )
    (comp (ref "R53")
      (value "100K")
      (footprint "RESC1608M")
      (description "Resistor - 0603; 0.063W; 1%")
      (fields (field (name "PART NUMBER") "10000045") (field (name "MANUFACTURER") "Multicomp"))
      (libsource (lib "HB_DB_Components") (part "Res"))
    )
    (comp (ref "R54")
      (value "100K")
      (footprint "RESC1608M")
      (description "Resistor - 0603; 0.063W; 1%")
      (fields (field (name "PART NUMBER") "10000045") (field (name "MANUFACTURER") "Multicomp"))
      (libsource (lib "HB_DB_Components") (part "Res"))
    )
    (comp (ref "R55")
      (value "10K")
      (footprint "RESC1608M")
      (description "Resistor - 0603; 0.063W; 1%")
      (fields (field (name "PART NUMBER") "10000044") (field (name "MANUFACTURER") "Multicomp"))
      (libsource (lib "HB_DB_Components") (part "Res"))
    )
    (comp (ref "R56")
      (value "100K")
      (footprint "RESC1608M")
      (description "Resistor - 0603; 0.063W; 1%")
      (fields
        (field (name "PART NUMBER") "10000045")
        (field (name "MANUFACTURER") "Multicomp")
        (field (name "POPULATE") "NP")
      )
      (libsource (lib "HB_DB_Components") (part "Res"))
    )
    (comp (ref "R57")
      (value "10K")
      (footprint "RESC1608M")
      (description "Resistor - 0603; 0.063W; 1%")
      (fields (field (name "PART NUMBER") "10000044") (field (name "MANUFACTURER") "Multicomp"))
      (libsource (lib "HB_DB_Components") (part "Res"))
    )
    (comp (ref "R58")
      (value "100K")
      (footprint "RESC1608M")
      (description "Resistor - 0603; 0.063W; 1%")
      (fields
        (field (name "PART NUMBER") "10000045")
        (field (name "MANUFACTURER") "Multicomp")
        (field (name "POPULATE") "NP")
      )
      (libsource (lib "HB_DB_Components") (part "Res"))
    )
    (comp (ref "R59")
      (value "10K")
      (footprint "RESC1608M")
      (description "Resistor")
      (fields (field (name "PART NUMBER") "10000044") (field (name "MANUFACTURER") "Multicomp"))
      (libsource (lib "HB_DB_Components") (part "Res"))
    )
    (comp (ref "R60")
      (value "274R")
      (footprint "RESC1608M")
      (description "Resistor")
      (fields (field (name "PART NUMBER") "10000041") (field (name "MANUFACTURER") "Multicomp"))
      (libsource (lib "HB_DB_Components") (part "Res"))
    )
    (comp (ref "R61")
      (value "274R")
      (footprint "RESC1608M")
      (description "Resistor - 0603; 0.063W; 1%")
      (fields (field (name "PART NUMBER") "10000041") (field (name "MANUFACTURER") "Multicomp"))
      (libsource (lib "HB_DB_Components") (part "Res"))
    )
    (comp (ref "R62")
      (value "100R")
      (footprint "RESC1608M")
      (description "Resistor - 0603; 0.063W; 1%")
      (fields (field (name "PART NUMBER") "10000042") (field (name "MANUFACTURER") "Multicomp"))
      (libsource (lib "HB_DB_Components") (part "Res"))
    )
    (comp (ref "R63")
      (value "100K")
      (footprint "RESC1608M")
      (description "Resistor - 0603; 0.063W; 1%")
      (fields (field (name "PART NUMBER") "10000045") (field (name "MANUFACTURER") "Multicomp"))
      (libsource (lib "HB_DB_Components") (part "Res"))
    )
    (comp (ref "R64")
      (value "10K")
      (footprint "RESC1608M")
      (description "Resistor - 0603; 0.063W; 1%")
      (fields (field (name "PART NUMBER") "10000044") (field (name "MANUFACTURER") "Multicomp"))
      (libsource (lib "HB_DB_Components") (part "Res"))
    )
    (comp (ref "R65")
      (value "100K")
      (footprint "RESC1608M")
      (description "Resistor - 0603; 0.063W; 1%")
      (fields (field (name "PART NUMBER") "10000045") (field (name "MANUFACTURER") "Multicomp"))
      (libsource (lib "HB_DB_Components") (part "Res"))
    )
    (comp (ref "R66")
      (value "4K7")
      (footprint "RESC1608M")
      (description "Resistor - 0603; 0.063W; 1%")
      (fields (field (name "PART NUMBER") "10000050") (field (name "MANUFACTURER") "Multicomp"))
      (libsource (lib "HB_DB_Components") (part "Res"))
    )
    (comp (ref "R67")
      (value "4K7")
      (footprint "RESC1608M")
      (description "Resistor - 0603; 0.063W; 1%")
      (fields (field (name "PART NUMBER") "10000050") (field (name "MANUFACTURER") "Multicomp"))
      (libsource (lib "HB_DB_Components") (part "Res"))
    )
    (comp (ref "R68")
      (value "100R")
      (footprint "RESC1608M")
      (description "Resistor - 0603; 0.063W; 1%")
      (fields (field (name "PART NUMBER") "10000042") (field (name "MANUFACTURER") "Multicomp"))
      (libsource (lib "HB_DB_Components") (part "Res"))
    )
    (comp (ref "R69")
      (value "100R")
      (footprint "RESC1608M")
      (description "Resistor - 0603; 0.063W; 1%")
      (fields (field (name "PART NUMBER") "10000042") (field (name "MANUFACTURER") "Multicomp"))
      (libsource (lib "HB_DB_Components") (part "Res"))
    )
    (comp (ref "R70")
      (value "10K")
      (footprint "RESC1608M")
      (description "Resistor - 0603; 0.063W; 1%")
      (fields (field (name "PART NUMBER") "10000044") (field (name "MANUFACTURER") "Multicomp"))
      (libsource (lib "HB_DB_Components") (part "Res"))
    )
    (comp (ref "R71")
      (value "10K")
      (footprint "RESC1608M")
      (description "Resistor - 0603; 0.063W; 1%")
      (fields (field (name "PART NUMBER") "10000044") (field (name "MANUFACTURER") "Multicomp"))
      (libsource (lib "HB_DB_Components") (part "Res"))
    )
    (comp (ref "R73")
      (value "6k8")
      (footprint "RESC2012L")
      (description "Resistor - 0805; 0.100W; 5%")
      (fields (field (name "PART NUMBER") "10000098"))
      (libsource (lib "HB_DB_Components") (part "Res"))
    )
    (comp (ref "R78")
      (value "6k8")
      (footprint "RESC2012L")
      (description "Resistor - 0805; 0.100W; 5%")
      (fields (field (name "PART NUMBER") "10000098"))
      (libsource (lib "HB_DB_Components") (part "Res"))
    )
    (comp (ref "R79")
      (value "6k8")
      (footprint "RESC2012L")
      (description "Resistor - 0805; 0.100W; 5%")
      (fields (field (name "PART NUMBER") "10000098"))
      (libsource (lib "HB_DB_Components") (part "Res"))
    )
    (comp (ref "R80")
      (value "6k8")
      (footprint "RESC2012L")
      (description "Resistor - 0805; 0.100W; 5%")
      (fields (field (name "PART NUMBER") "10000098"))
      (libsource (lib "HB_DB_Components") (part "Res"))
    )
    (comp (ref "R81")
      (value "6k8")
      (footprint "RESC2012L")
      (description "Resistor - 0805; 0.100W; 5%")
      (fields (field (name "PART NUMBER") "10000098"))
      (libsource (lib "HB_DB_Components") (part "Res"))
    )
    (comp (ref "R82")
      (value "6k8")
      (footprint "RESC2012L")
      (description "Resistor - 0805; 0.100W; 5%")
      (fields (field (name "PART NUMBER") "10000098"))
      (libsource (lib "HB_DB_Components") (part "Res"))
    )
    (comp (ref "R88")
      (value "680R")
      (footprint "RESC1608M")
      (description "Resistor - 0603; 0.063W; 1%")
      (fields (field (name "PART NUMBER") "10000061") (field (name "MANUFACTURER") "Multicomp"))
      (libsource (lib "HB_DB_Components") (part "Res"))
    )
    (comp (ref "R92")
      (value "10K")
      (footprint "RESC1608M")
      (description "Resistor - 0603; 0.063W; 1%")
      (fields (field (name "PART NUMBER") "10000044") (field (name "MANUFACTURER") "Multicomp"))
      (libsource (lib "HB_DB_Components") (part "Res"))
    )
    (comp (ref "R94")
      (value "10K")
      (footprint "RESC1608M")
      (description "Resistor - 0603; 0.063W; 1%")
      (fields (field (name "PART NUMBER") "10000044") (field (name "MANUFACTURER") "Multicomp"))
      (libsource (lib "HB_DB_Components") (part "Res"))
    )
    (comp (ref "R96")
      (value "6K8")
      (footprint "RESC1608M")
      (description "Resistor - 0603; 0.063W; 1%")
      (fields (field (name "PART NUMBER") "10000096"))
      (libsource (lib "HB_DB_Components") (part "Res"))
    )
    (comp (ref "R97")
      (value "10K")
      (footprint "RESC1608M")
      (description "Resistor - 0603; 0.063W; 1%")
      (fields (field (name "PART NUMBER") "10000044") (field (name "MANUFACTURER") "Multicomp"))
      (libsource (lib "HB_DB_Components") (part "Res"))
    )
    (comp (ref "R103")
      (value "6K8")
      (footprint "RESC1608M")
      (description "Resistor - 0603; 0.063W; 1%")
      (fields (field (name "PART NUMBER") "10000096"))
      (libsource (lib "HB_DB_Components") (part "Res"))
    )
    (comp (ref "R104")
      (value "10K")
      (footprint "RESC1608M")
      (description "Resistor - 0603; 0.063W; 1%")
      (fields (field (name "PART NUMBER") "10000044") (field (name "MANUFACTURER") "Multicomp"))
      (libsource (lib "HB_DB_Components") (part "Res"))
    )
    (comp (ref "R105")
      (value "680R")
      (footprint "RESC1608M")
      (description "Resistor - 0603; 0.063W; 1%")
      (fields
        (field (name "PART NUMBER") "10000061")
        (field (name "MANUFACTURER") "Multicomp")
        (field (name "POPULATE") "NP")
      )
      (libsource (lib "HB_DB_Components") (part "Res"))
    )
    (comp (ref "R106")
      (value "1K5")
      (footprint "RESC1608M")
      (description "Resistor - 0603; 0.063W; 1%")
      (fields (field (name "PART NUMBER") "10000048") (field (name "MANUFACTURER") "Multicomp"))
      (libsource (lib "HB_DB_Components") (part "Res"))
    )
    (comp (ref "R107")
      (value "100R")
      (footprint "RESC1608M")
      (description "Resistor - 0603; 0.063W; 1%")
      (fields (field (name "PART NUMBER") "10000042") (field (name "MANUFACTURER") "Multicomp"))
      (libsource (lib "HB_DB_Components") (part "Res"))
    )
    (comp (ref "R108")
      (value "6k8")
      (footprint "RESC2012L")
      (description "Resistor - 0805; 0.100W; 5%")
      (fields (field (name "PART NUMBER") "10000098"))
      (libsource (lib "HB_DB_Components") (part "Res"))
    )
    (comp (ref "R109")
      (value "6k8")
      (footprint "RESC2012L")
      (description "Resistor - 0805; 0.100W; 5%")
      (fields (field (name "PART NUMBER") "10000098"))
      (libsource (lib "HB_DB_Components") (part "Res"))
    )
    (comp (ref "R110")
      (value "6k8")
      (footprint "RESC2012L")
      (description "Resistor - 0805; 0.100W; 5%")
      (fields (field (name "PART NUMBER") "10000098"))
      (libsource (lib "HB_DB_Components") (part "Res"))
    )
    (comp (ref "R111")
      (value "6k8")
      (footprint "RESC2012L")
      (description "Resistor - 0805; 0.100W; 5%")
      (fields (field (name "PART NUMBER") "10000098"))
      (libsource (lib "HB_DB_Components") (part "Res"))
    )
    (comp (ref "R112")
      (value "6k8")
      (footprint "RESC2012L")
      (description "Resistor - 0805; 0.100W; 5%")
      (fields (field (name "PART NUMBER") "10000098"))
      (libsource (lib "HB_DB_Components") (part "Res"))
    )
    (comp (ref "R113")
      (value "6k8")
      (footprint "RESC2012L")
      (description "Resistor - 0805; 0.100W; 5%")
      (fields (field (name "PART NUMBER") "10000098"))
      (libsource (lib "HB_DB_Components") (part "Res"))
    )
    (comp (ref "R114")
      (value "6k8")
      (footprint "RESC2012L")
      (description "Resistor - 0805; 0.100W; 5%")
      (fields (field (name "PART NUMBER") "10000098"))
      (libsource (lib "HB_DB_Components") (part "Res"))
    )
    (comp (ref "U1")
      (value "A4988")
      (footprint "QFN50P500X500X100-28M")
      (description "A4988 (A4983 pinout compatible)")
      (fields (field (name "PART NUMBER") "10000094") (field (name "MANUFACTURER") "Allegro"))
      (libsource (lib "HB_DB_Components") (part "IC A4988"))
    )
    (comp (ref "U2")
      (value "A4988")
      (footprint "QFN50P500X500X100-28M")
      (description "A4988 (A4983 pinout compatible)")
      (fields (field (name "PART NUMBER") "10000094") (field (name "MANUFACTURER") "Allegro"))
      (libsource (lib "HB_DB_Components") (part "IC A4988"))
    )
    (comp (ref "U3")
      (value "A4988")
      (footprint "QFN50P500X500X100-28M")
      (description "A4988 (A4983 pinout compatible)")
      (fields (field (name "PART NUMBER") "10000094") (field (name "MANUFACTURER") "Allegro"))
      (libsource (lib "HB_DB_Components") (part "IC A4988"))
    )
    (comp (ref "U4")
      (value "A4988")
      (footprint "QFN50P500X500X100-28M")
      (description "A4988 (A4983 pinout compatible)")
      (fields (field (name "PART NUMBER") "10000094") (field (name "MANUFACTURER") "Allegro"))
      (libsource (lib "HB_DB_Components") (part "IC A4988"))
    )
    (comp (ref "U7")
      (value "Photo Switch")
      (footprint "OPIC_122x50x10")
      (description "Opto - Switch; OPIC Sharp; Slotted 3mm; Vcc 5v")
      (fields (field (name "PART NUMBER") "10000075") (field (name "MANUFACTURER") "Sharp"))
      (libsource (lib "HB_DB_Components") (part "Photo_Switch"))
    )
  )
  (nets
    (net (code "1") (name "/CTC1_Heat") (class "Default")
      (node (ref "R69") (pin "1") (pinfunction "1_1") (pintype "passive"))
      (node (ref "R92") (pin "2") (pinfunction "2_2") (pintype "passive"))
    )
    (net (code "2") (name "/CTC1_NTC1") (class "Default")
      (node (ref "J8") (pin "1") (pinfunction "1_1") (pintype "passive"))
      (node (ref "L2") (pin "2") (pinfunction "2_2") (pintype "passive"))
    )
    (net (code "3") (name "/CTC1_NTC2") (class "Default")
      (node (ref "J8") (pin "2") (pinfunction "2_2") (pintype "passive"))
      (node (ref "L4") (pin "2") (pinfunction "2_2") (pintype "passive"))
    )
    (net (code "4") (name "/CTC1_Temp") (class "Default")
      (node (ref "C39") (pin "2") (pinfunction "2_2") (pintype "passive"))
      (node (ref "C40") (pin "2") (pinfunction "2_2") (pintype "passive"))
      (node (ref "L2") (pin "1") (pinfunction "1_1") (pintype "passive"))
      (node (ref "R60") (pin "1") (pinfunction "1_1") (pintype "passive"))
    )
    (net (code "5") (name "/CTC2_Heat") (class "Default")
      (node (ref "R68") (pin "1") (pinfunction "1_1") (pintype "passive"))
      (node (ref "R70") (pin "2") (pinfunction "2_2") (pintype "passive"))
    )
    (net (code "6") (name "/CTC2_NTC1") (class "Default")
      (node (ref "J7") (pin "1") (pinfunction "1_1") (pintype "passive"))
      (node (ref "L1") (pin "2") (pinfunction "2_2") (pintype "passive"))
    )
    (net (code "7") (name "/CTC2_NTC2") (class "Default")
      (node (ref "J7") (pin "2") (pinfunction "2_2") (pintype "passive"))
      (node (ref "L3") (pin "2") (pinfunction "2_2") (pintype "passive"))
    )
    (net (code "8") (name "/CTC2_Temp") (class "Default")
      (node (ref "C37") (pin "2") (pinfunction "2_2") (pintype "passive"))
      (node (ref "C38") (pin "2") (pinfunction "2_2") (pintype "passive"))
      (node (ref "L1") (pin "1") (pinfunction "1_1") (pintype "passive"))
      (node (ref "R59") (pin "1") (pinfunction "1_1") (pintype "passive"))
    )
    (net (code "9") (name "/E1_Motor_1A") (class "Default")
      (node (ref "J5") (pin "2") (pinfunction "2_2") (pintype "passive"))
      (node (ref "R110") (pin "1") (pinfunction "1_1") (pintype "passive"))
      (node (ref "U4") (pin "24") (pinfunction "OUT1A_24") (pintype "passive"))
    )
    (net (code "10") (name "/E1_Motor_1B") (class "Default")
      (node (ref "J5") (pin "1") (pinfunction "1_1") (pintype "passive"))
      (node (ref "R108") (pin "1") (pinfunction "1_1") (pintype "passive"))
      (node (ref "U4") (pin "21") (pinfunction "OUT1B_21") (pintype "passive"))
    )
    (net (code "11") (name "/E1_Motor_2A") (class "Default")
      (node (ref "J5") (pin "3") (pinfunction "3_3") (pintype "passive"))
      (node (ref "R112") (pin "1") (pinfunction "1_1") (pintype "passive"))
      (node (ref "U4") (pin "26") (pinfunction "OUT2A_26") (pintype "passive"))
    )
    (net (code "12") (name "/E1_Motor_2B") (class "Default")
      (node (ref "J5") (pin "4") (pinfunction "4_4") (pintype "passive"))
      (node (ref "R114") (pin "1") (pinfunction "1_1") (pintype "passive"))
      (node (ref "U4") (pin "1") (pinfunction "OUT2B_1") (pintype "passive"))
    )
    (net (code "13") (name "/ME_DIR") (class "Default")
      (node (ref "J15") (pin "4") (pinfunction "4_4") (pintype "passive"))
      (node (ref "U4") (pin "19") (pinfunction "DIR_19") (pintype "input"))
    )
    (net (code "14") (name "/ME_EN") (class "Default")
      (node (ref "J15") (pin "3") (pinfunction "3_3") (pintype "passive"))
      (node (ref "U4") (pin "2") (pinfunction "ENABLE_2") (pintype "passive"))
    )
    (net (code "15") (name "/ME_STEP") (class "Default")
      (node (ref "J15") (pin "5") (pinfunction "5_5") (pintype "passive"))
      (node (ref "R54") (pin "2") (pinfunction "2_2") (pintype "passive"))
      (node (ref "U4") (pin "16") (pinfunction "STEP_16") (pintype "input"))
    )
    (net (code "16") (name "/MX_DIR") (class "Default")
      (node (ref "J12") (pin "4") (pinfunction "4_4") (pintype "passive"))
      (node (ref "U1") (pin "19") (pinfunction "DIR_19") (pintype "input"))
    )
    (net (code "17") (name "/MX_EN") (class "Default")
      (node (ref "J12") (pin "3") (pinfunction "3_3") (pintype "passive"))
      (node (ref "U1") (pin "2") (pinfunction "ENABLE_2") (pintype "passive"))
    )
    (net (code "18") (name "/MX_STEP") (class "Default")
      (node (ref "J12") (pin "5") (pinfunction "5_5") (pintype "passive"))
      (node (ref "R24") (pin "2") (pinfunction "2_2") (pintype "passive"))
      (node (ref "U1") (pin "16") (pinfunction "STEP_16") (pintype "input"))
    )
    (net (code "19") (name "/MY_DIR") (class "Default")
      (node (ref "J13") (pin "4") (pinfunction "4_4") (pintype "passive"))
      (node (ref "U2") (pin "19") (pinfunction "DIR_19") (pintype "input"))
    )
    (net (code "20") (name "/MY_EN") (class "Default")
      (node (ref "J13") (pin "3") (pinfunction "3_3") (pintype "passive"))
      (node (ref "U2") (pin "2") (pinfunction "ENABLE_2") (pintype "passive"))
    )
    (net (code "21") (name "/MY_STEP") (class "Default")
      (node (ref "J13") (pin "5") (pinfunction "5_5") (pintype "passive"))
      (node (ref "R25") (pin "2") (pinfunction "2_2") (pintype "passive"))
      (node (ref "U2") (pin "16") (pinfunction "STEP_16") (pintype "input"))
    )
    (net (code "22") (name "/MZ_DIR") (class "Default")
      (node (ref "J14") (pin "4") (pinfunction "4_4") (pintype "passive"))
      (node (ref "U3") (pin "19") (pinfunction "DIR_19") (pintype "input"))
    )
    (net (code "23") (name "/MZ_EN") (class "Default")
      (node (ref "J14") (pin "3") (pinfunction "3_3") (pintype "passive"))
      (node (ref "U3") (pin "2") (pinfunction "ENABLE_2") (pintype "passive"))
    )
    (net (code "24") (name "/MZ_STEP") (class "Default")
      (node (ref "J14") (pin "5") (pinfunction "5_5") (pintype "passive"))
      (node (ref "R53") (pin "2") (pinfunction "2_2") (pintype "passive"))
      (node (ref "U3") (pin "16") (pinfunction "STEP_16") (pintype "input"))
    )
    (net (code "25") (name "/Mn_RST") (class "Default")
      (node (ref "J12") (pin "2") (pinfunction "2_2") (pintype "passive"))
      (node (ref "J13") (pin "2") (pinfunction "2_2") (pintype "passive"))
      (node (ref "J14") (pin "2") (pinfunction "2_2") (pintype "passive"))
      (node (ref "J15") (pin "2") (pinfunction "2_2") (pintype "passive"))
      (node (ref "U1") (pin "12") (pinfunction "RESET_12") (pintype "passive"))
      (node (ref "U2") (pin "12") (pinfunction "RESET_12") (pintype "passive"))
      (node (ref "U3") (pin "12") (pinfunction "RESET_12") (pintype "passive"))
      (node (ref "U4") (pin "12") (pinfunction "RESET_12") (pintype "passive"))
    )
    (net (code "26") (name "/Opto_X_IN") (class "Default")
      (node (ref "R44") (pin "2") (pinfunction "2_2") (pintype "passive"))
      (node (ref "R64") (pin "2") (pinfunction "2_2") (pintype "passive"))
    )
    (net (code "27") (name "/Opto_Y_IN") (class "Default")
      (node (ref "R96") (pin "2") (pinfunction "2_2") (pintype "passive"))
      (node (ref "R97") (pin "2") (pinfunction "2_2") (pintype "passive"))
    )
    (net (code "28") (name "/Opto_Z_IN") (class "Default")
      (node (ref "R103") (pin "2") (pinfunction "2_2") (pintype "passive"))
      (node (ref "R104") (pin "2") (pinfunction "2_2") (pintype "passive"))
    )
    (net (code "29") (name "/Thermocouple") (class "Default")
      (node (ref "C69") (pin "2") (pinfunction "2_2") (pintype "passive"))
      (node (ref "L10") (pin "1") (pinfunction "1_1") (pintype "passive"))
    )
    (net (code "30") (name "/X5V") (class "Default")
      (node (ref "C42") (pin "2") (pinfunction "2_2") (pintype "passive"))
      (node (ref "C68") (pin "2") (pinfunction "2_2") (pintype "passive"))
      (node (ref "J16") (pin "1") (pinfunction "1_1") (pintype "passive"))
      (node (ref "J16") (pin "2") (pinfunction "2_2") (pintype "passive"))
      (node (ref "R105") (pin "2") (pinfunction "2_2") (pintype "passive"))
      (node (ref "R14") (pin "2") (pinfunction "2_2") (pintype "passive"))
      (node (ref "R88") (pin "2") (pinfunction "2_2") (pintype "passive"))
      (node (ref "U7") (pin "3") (pinfunction "Vcc_3") (pintype "power_in"))
    )
    (net (code "31") (name "/X_Motor_1A") (class "Default")
      (node (ref "J1") (pin "2") (pinfunction "2_2") (pintype "passive"))
      (node (ref "R40") (pin "1") (pinfunction "1_1") (pintype "passive"))
      (node (ref "U1") (pin "24") (pinfunction "OUT1A_24") (pintype "passive"))
    )
    (net (code "32") (name "/X_Motor_1B") (class "Default")
      (node (ref "J1") (pin "1") (pinfunction "1_1") (pintype "passive"))
      (node (ref "R34") (pin "1") (pinfunction "1_1") (pintype "passive"))
      (node (ref "U1") (pin "21") (pinfunction "OUT1B_21") (pintype "passive"))
    )
    (net (code "33") (name "/X_Motor_2A") (class "Default")
      (node (ref "J1") (pin "3") (pinfunction "3_3") (pintype "passive"))
      (node (ref "R78") (pin "1") (pinfunction "1_1") (pintype "passive"))
      (node (ref "U1") (pin "26") (pinfunction "OUT2A_26") (pintype "passive"))
    )
    (net (code "34") (name "/X_Motor_2B") (class "Default")
      (node (ref "J1") (pin "4") (pinfunction "4_4") (pintype "passive"))
      (node (ref "R80") (pin "1") (pinfunction "1_1") (pintype "passive"))
      (node (ref "U1") (pin "1") (pinfunction "OUT2B_1") (pintype "passive"))
    )
    (net (code "35") (name "/Xgnd") (class "Default")
      (node (ref "C42") (pin "1") (pinfunction "1_1") (pintype "passive"))
      (node (ref "C68") (pin "1") (pinfunction "1_1") (pintype "passive"))
      (node (ref "J16") (pin "5") (pinfunction "5_5") (pintype "passive"))
      (node (ref "J16") (pin "6") (pinfunction "6_6") (pintype "passive"))
      (node (ref "U7") (pin "2") (pinfunction "K_2") (pintype "passive"))
      (node (ref "U7") (pin "5") (pinfunction "GND_5") (pintype "power_in"))
    )
    (net (code "36") (name "/Xout") (class "Default")
      (node (ref "D14") (pin "1") (pinfunction "K_1") (pintype "passive"))
      (node (ref "J16") (pin "3") (pinfunction "3_3") (pintype "passive"))
      (node (ref "J16") (pin "4") (pinfunction "4_4") (pintype "passive"))
      (node (ref "R105") (pin "1") (pinfunction "1_1") (pintype "passive"))
      (node (ref "U7") (pin "4") (pinfunction "Out_4") (pintype "output"))
    )
    (net (code "37") (name "/Y_Motor_1A") (class "Default")
      (node (ref "J2") (pin "2") (pinfunction "2_2") (pintype "passive"))
      (node (ref "R73") (pin "1") (pinfunction "1_1") (pintype "passive"))
      (node (ref "U2") (pin "24") (pinfunction "OUT1A_24") (pintype "passive"))
    )
    (net (code "38") (name "/Y_Motor_1B") (class "Default")
      (node (ref "J2") (pin "1") (pinfunction "1_1") (pintype "passive"))
      (node (ref "R39") (pin "1") (pinfunction "1_1") (pintype "passive"))
      (node (ref "U2") (pin "21") (pinfunction "OUT1B_21") (pintype "passive"))
    )
    (net (code "39") (name "/Y_Motor_2A") (class "Default")
      (node (ref "J2") (pin "3") (pinfunction "3_3") (pintype "passive"))
      (node (ref "R79") (pin "1") (pinfunction "1_1") (pintype "passive"))
      (node (ref "U2") (pin "26") (pinfunction "OUT2A_26") (pintype "passive"))
    )
    (net (code "40") (name "/Y_Motor_2B") (class "Default")
      (node (ref "J2") (pin "4") (pinfunction "4_4") (pintype "passive"))
      (node (ref "R81") (pin "1") (pinfunction "1_1") (pintype "passive"))
      (node (ref "U2") (pin "1") (pinfunction "OUT2B_1") (pintype "passive"))
    )
    (net (code "41") (name "/Z_Motor_1A") (class "Default")
      (node (ref "J4") (pin "2") (pinfunction "2_2") (pintype "passive"))
      (node (ref "R109") (pin "1") (pinfunction "1_1") (pintype "passive"))
      (node (ref "U3") (pin "24") (pinfunction "OUT1A_24") (pintype "passive"))
    )
    (net (code "42") (name "/Z_Motor_1B") (class "Default")
      (node (ref "J4") (pin "1") (pinfunction "1_1") (pintype "passive"))
      (node (ref "R82") (pin "1") (pinfunction "1_1") (pintype "passive"))
      (node (ref "U3") (pin "21") (pinfunction "OUT1B_21") (pintype "passive"))
    )
    (net (code "43") (name "/Z_Motor_2A") (class "Default")
      (node (ref "J4") (pin "3") (pinfunction "3_3") (pintype "passive"))
      (node (ref "R111") (pin "1") (pinfunction "1_1") (pintype "passive"))
      (node (ref "U3") (pin "26") (pinfunction "OUT2A_26") (pintype "passive"))
    )
    (net (code "44") (name "/Z_Motor_2B") (class "Default")
      (node (ref "J4") (pin "4") (pinfunction "4_4") (pintype "passive"))
      (node (ref "R113") (pin "1") (pinfunction "1_1") (pintype "passive"))
      (node (ref "U3") (pin "1") (pinfunction "OUT2B_1") (pintype "passive"))
    )
    (net (code "45") (name "GND") (class "Default")
      (node (ref "C10") (pin "1") (pinfunction "1_1") (pintype "passive"))
      (node (ref "C11") (pin "2") (pinfunction "2_2") (pintype "passive"))
      (node (ref "C12") (pin "2") (pinfunction "2_2") (pintype "passive"))
      (node (ref "C15") (pin "1") (pinfunction "1_1") (pintype "passive"))
      (node (ref "C16") (pin "1") (pinfunction "1_1") (pintype "passive"))
      (node (ref "C17") (pin "1") (pinfunction "1_1") (pintype "passive"))
      (node (ref "C18") (pin "2") (pinfunction "2_2") (pintype "passive"))
      (node (ref "C21") (pin "1") (pinfunction "1_1") (pintype "passive"))
      (node (ref "C22") (pin "1") (pinfunction "1_1") (pintype "passive"))
      (node (ref "C23") (pin "1") (pinfunction "1_1") (pintype "passive"))
      (node (ref "C24") (pin "1") (pinfunction "1_1") (pintype "passive"))
      (node (ref "C25") (pin "1") (pinfunction "1_1") (pintype "passive"))
      (node (ref "C26") (pin "1") (pinfunction "1_1") (pintype "passive"))
      (node (ref "C27") (pin "2") (pinfunction "2_2") (pintype "passive"))
      (node (ref "C28") (pin "1") (pinfunction "1_1") (pintype "passive"))
      (node (ref "C29") (pin "1") (pinfunction "1_1") (pintype "passive"))
      (node (ref "C3") (pin "1") (pinfunction "1_1") (pintype "passive"))
      (node (ref "C31") (pin "2") (pinfunction "2_2") (pintype "passive"))
      (node (ref "C33") (pin "1") (pinfunction "1_1") (pintype "passive"))
      (node (ref "C34") (pin "1") (pinfunction "1_1") (pintype "passive"))
      (node (ref "C35") (pin "1") (pinfunction "1_1") (pintype "passive"))
      (node (ref "C36") (pin "1") (pinfunction "1_1") (pintype "passive"))
      (node (ref "C4") (pin "1") (pinfunction "1_1") (pintype "passive"))
      (node (ref "C5") (pin "1") (pinfunction "1_1") (pintype "passive"))
      (node (ref "C6") (pin "1") (pinfunction "1_1") (pintype "passive"))
      (node (ref "C62") (pin "1") (pinfunction "1_1") (pintype "passive"))
      (node (ref "C7") (pin "2") (pinfunction "2_2") (pintype "passive"))
      (node (ref "C8") (pin "1") (pinfunction "1_1") (pintype "passive"))
      (node (ref "C9") (pin "1") (pinfunction "1_1") (pintype "passive"))
      (node (ref "D17") (pin "2") (pinfunction "A_2") (pintype "passive"))
      (node (ref "D18") (pin "2") (pinfunction "A_2") (pintype "passive"))
      (node (ref "J12") (pin "6") (pinfunction "6_6") (pintype "passive"))
      (node (ref "J13") (pin "6") (pinfunction "6_6") (pintype "passive"))
      (node (ref "J14") (pin "6") (pinfunction "6_6") (pintype "passive"))
      (node (ref "J15") (pin "6") (pinfunction "6_6") (pintype "passive"))
      (node (ref "J21") (pin "2") (pinfunction "2_2") (pintype "passive"))
      (node (ref "J3") (pin "5") (pinfunction "5_5") (pintype "passive"))
      (node (ref "J3") (pin "6") (pinfunction "6_6") (pintype "passive"))
      (node (ref "J6") (pin "5") (pinfunction "5_5") (pintype "passive"))
      (node (ref "J6") (pin "6") (pinfunction "6_6") (pintype "passive"))
      (node (ref "J9") (pin "5") (pinfunction "5_5") (pintype "passive"))
      (node (ref "J9") (pin "6") (pinfunction "6_6") (pintype "passive"))
      (node (ref "P1") (pin "1") (pinfunction "TOP_1") (pintype "passive"))
      (node (ref "P2") (pin "1") (pinfunction "TOP_1") (pintype "passive"))
      (node (ref "P3") (pin "1") (pinfunction "TOP_1") (pintype "passive"))
      (node (ref "P4") (pin "1") (pinfunction "TOP_1") (pintype "passive"))
      (node (ref "Q1") (pin "2") (pinfunction "S_2") (pintype "passive"))
      (node (ref "Q10") (pin "2") (pinfunction "S_2") (pintype "passive"))
      (node (ref "Q12") (pin "2") (pinfunction "S_2") (pintype "passive"))
      (node (ref "Q2") (pin "2") (pinfunction "S_2") (pintype "passive"))
      (node (ref "Q3") (pin "2") (pinfunction "S_2") (pintype "passive"))
      (node (ref "Q4") (pin "2") (pinfunction "S_2") (pintype "passive"))
      (node (ref "Q5") (pin "3") (pinfunction "S_3") (pintype "passive"))
      (node (ref "Q6") (pin "3") (pinfunction "S_3") (pintype "passive"))
      (node (ref "R104") (pin "1") (pinfunction "1_1") (pintype "passive"))
      (node (ref "R108") (pin "2") (pinfunction "2_2") (pintype "passive"))
      (node (ref "R109") (pin "2") (pinfunction "2_2") (pintype "passive"))
      (node (ref "R110") (pin "2") (pinfunction "2_2") (pintype "passive"))
      (node (ref "R111") (pin "2") (pinfunction "2_2") (pintype "passive"))
      (node (ref "R112") (pin "2") (pinfunction "2_2") (pintype "passive"))
      (node (ref "R113") (pin "2") (pinfunction "2_2") (pintype "passive"))
      (node (ref "R114") (pin "2") (pinfunction "2_2") (pintype "passive"))
      (node (ref "R20") (pin "1") (pinfunction "1_1") (pintype "passive"))
      (node (ref "R21") (pin "1") (pinfunction "1_1") (pintype "passive"))
      (node (ref "R22") (pin "1") (pinfunction "1_1") (pintype "passive"))
      (node (ref "R23") (pin "1") (pinfunction "1_1") (pintype "passive"))
      (node (ref "R26") (pin "1") (pinfunction "1_1") (pintype "passive"))
      (node (ref "R27") (pin "1") (pinfunction "1_1") (pintype "passive"))
      (node (ref "R28") (pin "1") (pinfunction "1_1") (pintype "passive"))
      (node (ref "R29") (pin "1") (pinfunction "1_1") (pintype "passive"))
      (node (ref "R34") (pin "2") (pinfunction "2_2") (pintype "passive"))
      (node (ref "R39") (pin "2") (pinfunction "2_2") (pintype "passive"))
      (node (ref "R40") (pin "2") (pinfunction "2_2") (pintype "passive"))
      (node (ref "R49") (pin "1") (pinfunction "1_1") (pintype "passive"))
      (node (ref "R50") (pin "1") (pinfunction "1_1") (pintype "passive"))
      (node (ref "R51") (pin "1") (pinfunction "1_1") (pintype "passive"))
      (node (ref "R52") (pin "1") (pinfunction "1_1") (pintype "passive"))
      (node (ref "R55") (pin "1") (pinfunction "1_1") (pintype "passive"))
      (node (ref "R56") (pin "1") (pinfunction "1_1") (pintype "passive"))
      (node (ref "R57") (pin "1") (pinfunction "1_1") (pintype "passive"))
      (node (ref "R58") (pin "1") (pinfunction "1_1") (pintype "passive"))
      (node (ref "R64") (pin "1") (pinfunction "1_1") (pintype "passive"))
      (node (ref "R70") (pin "1") (pinfunction "1_1") (pintype "passive"))
      (node (ref "R71") (pin "1") (pinfunction "1_1") (pintype "passive"))
      (node (ref "R73") (pin "2") (pinfunction "2_2") (pintype "passive"))
      (node (ref "R78") (pin "2") (pinfunction "2_2") (pintype "passive"))
      (node (ref "R79") (pin "2") (pinfunction "2_2") (pintype "passive"))
      (node (ref "R80") (pin "2") (pinfunction "2_2") (pintype "passive"))
      (node (ref "R81") (pin "2") (pinfunction "2_2") (pintype "passive"))
      (node (ref "R82") (pin "2") (pinfunction "2_2") (pintype "passive"))
      (node (ref "R92") (pin "1") (pinfunction "1_1") (pintype "passive"))
      (node (ref "R94") (pin "1") (pinfunction "1_1") (pintype "passive"))
      (node (ref "R97") (pin "1") (pinfunction "1_1") (pintype "passive"))
      (node (ref "U1") (pin "18") (pinfunction "GND_18") (pintype "passive"))
      (node (ref "U1") (pin "29") (pinfunction "PAD_29") (pintype "passive"))
      (node (ref "U1") (pin "3") (pinfunction "GND_3") (pintype "passive"))
      (node (ref "U2") (pin "18") (pinfunction "GND_18") (pintype "passive"))
      (node (ref "U2") (pin "29") (pinfunction "PAD_29") (pintype "passive"))
      (node (ref "U2") (pin "3") (pinfunction "GND_3") (pintype "passive"))
      (node (ref "U3") (pin "18") (pinfunction "GND_18") (pintype "passive"))
      (node (ref "U3") (pin "29") (pinfunction "PAD_29") (pintype "passive"))
      (node (ref "U3") (pin "3") (pinfunction "GND_3") (pintype "passive"))
      (node (ref "U4") (pin "18") (pinfunction "GND_18") (pintype "passive"))
      (node (ref "U4") (pin "29") (pinfunction "PAD_29") (pintype "passive"))
      (node (ref "U4") (pin "3") (pinfunction "GND_3") (pintype "passive"))
    )
    (net (code "46") (name "GND_A") (class "Default")
      (node (ref "C37") (pin "1") (pinfunction "1_1") (pintype "passive"))
      (node (ref "C38") (pin "1") (pinfunction "1_1") (pintype "passive"))
      (node (ref "C39") (pin "1") (pinfunction "1_1") (pintype "passive"))
      (node (ref "C40") (pin "1") (pinfunction "1_1") (pintype "passive"))
      (node (ref "C69") (pin "1") (pinfunction "1_1") (pintype "passive"))
      (node (ref "L11") (pin "1") (pinfunction "1_1") (pintype "passive"))
      (node (ref "L3") (pin "1") (pinfunction "1_1") (pintype "passive"))
      (node (ref "L4") (pin "1") (pinfunction "1_1") (pintype "passive"))
    )
    (net (code "47") (name "Net-(D1-A)") (class "Default")
      (node (ref "D1") (pin "2") (pinfunction "A_2") (pintype "passive"))
      (node (ref "R13") (pin "1") (pinfunction "1_1") (pintype "passive"))
    )
    (net (code "48") (name "Net-(D1-K)") (class "Default")
      (node (ref "D1") (pin "1") (pinfunction "K_1") (pintype "passive"))
      (node (ref "J3") (pin "3") (pinfunction "3_3") (pintype "passive"))
      (node (ref "J3") (pin "4") (pinfunction "4_4") (pintype "passive"))
      (node (ref "R44") (pin "1") (pinfunction "1_1") (pintype "passive"))
    )
    (net (code "49") (name "Net-(D2-K)") (class "Default")
      (node (ref "D2") (pin "1") (pinfunction "K_1") (pintype "passive"))
      (node (ref "R16") (pin "2") (pinfunction "2_2") (pintype "passive"))
    )
    (net (code "50") (name "Net-(D3-K)") (class "Default")
      (node (ref "D3") (pin "1") (pinfunction "K_1") (pintype "passive"))
      (node (ref "R17") (pin "2") (pinfunction "2_2") (pintype "passive"))
    )
    (net (code "51") (name "Net-(D4-A)") (class "Default")
      (node (ref "D4") (pin "2") (pinfunction "A_2") (pintype "passive"))
      (node (ref "R42") (pin "1") (pinfunction "1_1") (pintype "passive"))
    )
    (net (code "52") (name "Net-(D4-K)") (class "Default")
      (node (ref "D4") (pin "1") (pinfunction "K_1") (pintype "passive"))
      (node (ref "J6") (pin "3") (pinfunction "3_3") (pintype "passive"))
      (node (ref "J6") (pin "4") (pinfunction "4_4") (pintype "passive"))
      (node (ref "R96") (pin "1") (pinfunction "1_1") (pintype "passive"))
    )
    (net (code "53") (name "Net-(D5-K)") (class "Default")
      (node (ref "D5") (pin "1") (pinfunction "K_1") (pintype "passive"))
      (node (ref "R46") (pin "2") (pinfunction "2_2") (pintype "passive"))
    )
    (net (code "54") (name "Net-(D6-K)") (class "Default")
      (node (ref "D6") (pin "1") (pinfunction "K_1") (pintype "passive"))
      (node (ref "R61") (pin "2") (pinfunction "2_2") (pintype "passive"))
    )
    (net (code "55") (name "Net-(D7-A)") (class "Default")
      (node (ref "D7") (pin "2") (pinfunction "A_2") (pintype "passive"))
      (node (ref "R45") (pin "1") (pinfunction "1_1") (pintype "passive"))
    )
    (net (code "56") (name "Net-(D7-K)") (class "Default")
      (node (ref "D7") (pin "1") (pinfunction "K_1") (pintype "passive"))
      (node (ref "J9") (pin "3") (pinfunction "3_3") (pintype "passive"))
      (node (ref "J9") (pin "4") (pinfunction "4_4") (pintype "passive"))
      (node (ref "R103") (pin "1") (pinfunction "1_1") (pintype "passive"))
    )
    (net (code "57") (name "Net-(D8-A)") (class "Default")
      (node (ref "D8") (pin "2") (pinfunction "A_2") (pintype "passive"))
      (node (ref "R66") (pin "1") (pinfunction "1_1") (pintype "passive"))
    )
    (net (code "58") (name "Net-(D8-K)") (class "Default")
      (node (ref "D8") (pin "1") (pinfunction "K_1") (pintype "passive"))
      (node (ref "Q12") (pin "3") (pinfunction "D_3") (pintype "passive"))
      (node (ref "R107") (pin "1") (pinfunction "1_1") (pintype "passive"))
      (node (ref "R63") (pin "1") (pinfunction "1_1") (pintype "passive"))
    )
    (net (code "59") (name "Net-(D9-A)") (class "Default")
      (node (ref "D9") (pin "2") (pinfunction "A_2") (pintype "passive"))
      (node (ref "R67") (pin "1") (pinfunction "1_1") (pintype "passive"))
    )
    (net (code "60") (name "Net-(D9-K)") (class "Default")
      (node (ref "D9") (pin "1") (pinfunction "K_1") (pintype "passive"))
      (node (ref "Q10") (pin "3") (pinfunction "D_3") (pintype "passive"))
      (node (ref "R62") (pin "1") (pinfunction "1_1") (pintype "passive"))
      (node (ref "R65") (pin "1") (pinfunction "1_1") (pintype "passive"))
    )
    (net (code "61") (name "Net-(D14-A)") (class "Default")
      (node (ref "D14") (pin "2") (pinfunction "A_2") (pintype "passive"))
      (node (ref "R88") (pin "1") (pinfunction "1_1") (pintype "passive"))
    )
    (net (code "62") (name "Net-(D15-A)") (class "Default")
      (node (ref "D15") (pin "2") (pinfunction "A_2") (pintype "passive"))
      (node (ref "J8") (pin "4") (pinfunction "4_4") (pintype "passive"))
      (node (ref "Q5") (pin "2") (pinfunction "D_2") (pintype "passive"))
    )
    (net (code "63") (name "Net-(D16-A)") (class "Default")
      (node (ref "D16") (pin "2") (pinfunction "A_2") (pintype "passive"))
      (node (ref "J7") (pin "4") (pinfunction "4_4") (pintype "passive"))
      (node (ref "Q6") (pin "2") (pinfunction "D_2") (pintype "passive"))
    )
    (net (code "64") (name "Net-(D17-K)") (class "Default")
      (node (ref "D17") (pin "1") (pinfunction "K_1") (pintype "passive"))
      (node (ref "Q9") (pin "2") (pinfunction "S_2") (pintype "passive"))
      (node (ref "R43") (pin "1") (pinfunction "1_1") (pintype "passive"))
      (node (ref "R65") (pin "2") (pinfunction "2_2") (pintype "passive"))
    )
    (net (code "65") (name "Net-(D18-K)") (class "Default")
      (node (ref "D18") (pin "1") (pinfunction "K_1") (pintype "passive"))
      (node (ref "Q11") (pin "2") (pinfunction "S_2") (pintype "passive"))
      (node (ref "R106") (pin "1") (pinfunction "1_1") (pintype "passive"))
      (node (ref "R63") (pin "2") (pinfunction "2_2") (pintype "passive"))
    )
    (net (code "66") (name "Net-(J17-Pad1)") (class "Default")
      (node (ref "J17") (pin "1") (pinfunction "1_1") (pintype "passive"))
      (node (ref "L11") (pin "2") (pinfunction "2_2") (pintype "passive"))
      (node (ref "R10") (pin "2") (pinfunction "2_2") (pintype "passive"))
    )
    (net (code "67") (name "Net-(J17-Pad3)") (class "Default")
      (node (ref "J17") (pin "3") (pinfunction "3_3") (pintype "passive"))
      (node (ref "R5") (pin "2") (pinfunction "2_2") (pintype "passive"))
    )
    (net (code "68") (name "Net-(L10-Pad2)") (class "Default")
      (node (ref "L10") (pin "2") (pinfunction "2_2") (pintype "passive"))
      (node (ref "R10") (pin "1") (pinfunction "1_1") (pintype "passive"))
      (node (ref "R5") (pin "1") (pinfunction "1_1") (pintype "passive"))
    )
    (net (code "69") (name "Net-(P1-BOT)") (class "Default")
      (node (ref "C17") (pin "2") (pinfunction "2_2") (pintype "passive"))
      (node (ref "P1") (pin "2") (pinfunction "BOT_2") (pintype "passive"))
      (node (ref "R18") (pin "1") (pinfunction "1_1") (pintype "passive"))
    )
    (net (code "70") (name "Net-(P1-TAP)") (class "Default")
      (node (ref "P1") (pin "3") (pinfunction "TAP_3") (pintype "passive"))
      (node (ref "U1") (pin "17") (pinfunction "REF_17") (pintype "passive"))
    )
    (net (code "71") (name "Net-(P2-BOT)") (class "Default")
      (node (ref "C18") (pin "1") (pinfunction "1_1") (pintype "passive"))
      (node (ref "P2") (pin "2") (pinfunction "BOT_2") (pintype "passive"))
      (node (ref "R19") (pin "1") (pinfunction "1_1") (pintype "passive"))
    )
    (net (code "72") (name "Net-(P2-TAP)") (class "Default")
      (node (ref "P2") (pin "3") (pinfunction "TAP_3") (pintype "passive"))
      (node (ref "U2") (pin "17") (pinfunction "REF_17") (pintype "passive"))
    )
    (net (code "73") (name "Net-(P3-BOT)") (class "Default")
      (node (ref "C35") (pin "2") (pinfunction "2_2") (pintype "passive"))
      (node (ref "P3") (pin "2") (pinfunction "BOT_2") (pintype "passive"))
      (node (ref "R47") (pin "1") (pinfunction "1_1") (pintype "passive"))
    )
    (net (code "74") (name "Net-(P3-TAP)") (class "Default")
      (node (ref "P3") (pin "3") (pinfunction "TAP_3") (pintype "passive"))
      (node (ref "U3") (pin "17") (pinfunction "REF_17") (pintype "passive"))
    )
    (net (code "75") (name "Net-(P4-BOT)") (class "Default")
      (node (ref "C36") (pin "2") (pinfunction "2_2") (pintype "passive"))
      (node (ref "P4") (pin "2") (pinfunction "BOT_2") (pintype "passive"))
      (node (ref "R48") (pin "1") (pinfunction "1_1") (pintype "passive"))
    )
    (net (code "76") (name "Net-(P4-TAP)") (class "Default")
      (node (ref "P4") (pin "3") (pinfunction "TAP_3") (pintype "passive"))
      (node (ref "U4") (pin "17") (pinfunction "REF_17") (pintype "passive"))
    )
    (net (code "77") (name "Net-(Q1-D)") (class "Default")
      (node (ref "Q1") (pin "3") (pinfunction "D_3") (pintype "passive"))
      (node (ref "R16") (pin "1") (pinfunction "1_1") (pintype "passive"))
    )
    (net (code "78") (name "Net-(Q1-G)") (class "Default")
      (node (ref "Q1") (pin "1") (pinfunction "G_1") (pintype "passive"))
      (node (ref "R24") (pin "1") (pinfunction "1_1") (pintype "passive"))
    )
    (net (code "79") (name "Net-(Q2-D)") (class "Default")
      (node (ref "Q2") (pin "3") (pinfunction "D_3") (pintype "passive"))
      (node (ref "R17") (pin "1") (pinfunction "1_1") (pintype "passive"))
    )
    (net (code "80") (name "Net-(Q2-G)") (class "Default")
      (node (ref "Q2") (pin "1") (pinfunction "G_1") (pintype "passive"))
      (node (ref "R25") (pin "1") (pinfunction "1_1") (pintype "passive"))
    )
    (net (code "81") (name "Net-(Q3-D)") (class "Default")
      (node (ref "Q3") (pin "3") (pinfunction "D_3") (pintype "passive"))
      (node (ref "R46") (pin "1") (pinfunction "1_1") (pintype "passive"))
    )
    (net (code "82") (name "Net-(Q3-G)") (class "Default")
      (node (ref "Q3") (pin "1") (pinfunction "G_1") (pintype "passive"))
      (node (ref "R53") (pin "1") (pinfunction "1_1") (pintype "passive"))
    )
    (net (code "83") (name "Net-(Q4-D)") (class "Default")
      (node (ref "Q4") (pin "3") (pinfunction "D_3") (pintype "passive"))
      (node (ref "R61") (pin "1") (pinfunction "1_1") (pintype "passive"))
    )
    (net (code "84") (name "Net-(Q4-G)") (class "Default")
      (node (ref "Q4") (pin "1") (pinfunction "G_1") (pintype "passive"))
      (node (ref "R54") (pin "1") (pinfunction "1_1") (pintype "passive"))
    )
    (net (code "85") (name "Net-(Q5-G)") (class "Default")
      (node (ref "Q5") (pin "1") (pinfunction "G_1") (pintype "passive"))
      (node (ref "Q9") (pin "3") (pinfunction "D_3") (pintype "passive"))
      (node (ref "R71") (pin "2") (pinfunction "2_2") (pintype "passive"))
    )
    (net (code "86") (name "Net-(Q9-G)") (class "Default")
      (node (ref "Q9") (pin "1") (pinfunction "G_1") (pintype "passive"))
      (node (ref "R62") (pin "2") (pinfunction "2_2") (pintype "passive"))
    )
    (net (code "87") (name "Net-(Q10-G)") (class "Default")
      (node (ref "Q10") (pin "1") (pinfunction "G_1") (pintype "passive"))
      (node (ref "R69") (pin "2") (pinfunction "2_2") (pintype "passive"))
    )
    (net (code "88") (name "Net-(Q11-D)") (class "Default")
      (node (ref "Q11") (pin "3") (pinfunction "D_3") (pintype "passive"))
      (node (ref "Q6") (pin "1") (pinfunction "G_1") (pintype "passive"))
      (node (ref "R94") (pin "2") (pinfunction "2_2") (pintype "passive"))
    )
    (net (code "89") (name "Net-(Q11-G)") (class "Default")
      (node (ref "Q11") (pin "1") (pinfunction "G_1") (pintype "passive"))
      (node (ref "R107") (pin "2") (pinfunction "2_2") (pintype "passive"))
    )
    (net (code "90") (name "Net-(Q12-G)") (class "Default")
      (node (ref "Q12") (pin "1") (pinfunction "G_1") (pintype "passive"))
      (node (ref "R68") (pin "2") (pinfunction "2_2") (pintype "passive"))
    )
    (net (code "91") (name "Net-(U1-CP1)") (class "Default")
      (node (ref "C1") (pin "2") (pinfunction "2_2") (pintype "passive"))
      (node (ref "U1") (pin "4") (pinfunction "CP1_4") (pintype "passive"))
    )
    (net (code "92") (name "Net-(U1-CP2)") (class "Default")
      (node (ref "C1") (pin "1") (pinfunction "1_1") (pintype "passive"))
      (node (ref "U1") (pin "5") (pinfunction "CP2_5") (pintype "passive"))
    )
    (net (code "93") (name "Net-(U1-MS1)") (class "Default")
      (node (ref "R1") (pin "1") (pinfunction "1_1") (pintype "passive"))
      (node (ref "R28") (pin "2") (pinfunction "2_2") (pintype "passive"))
      (node (ref "U1") (pin "9") (pinfunction "MS1_9") (pintype "input"))
    )
    (net (code "94") (name "Net-(U1-MS2)") (class "Default")
      (node (ref "R2") (pin "1") (pinfunction "1_1") (pintype "passive"))
      (node (ref "U1") (pin "10") (pinfunction "MS2_10") (pintype "input"))
    )
    (net (code "95") (name "Net-(U1-MS3)") (class "Default")
      (node (ref "R3") (pin "1") (pinfunction "1_1") (pintype "passive"))
      (node (ref "U1") (pin "11") (pinfunction "MS3_11") (pintype "input"))
    )
    (net (code "96") (name "Net-(U1-ROSC)") (class "Default")
      (node (ref "R26") (pin "2") (pinfunction "2_2") (pintype "passive"))
      (node (ref "U1") (pin "13") (pinfunction "ROSC_13") (pintype "passive"))
    )
    (net (code "97") (name "Net-(U1-SENSE1)") (class "Default")
      (node (ref "R21") (pin "2") (pinfunction "2_2") (pintype "passive"))
      (node (ref "U1") (pin "23") (pinfunction "SENSE1_23") (pintype "passive"))
    )
    (net (code "98") (name "Net-(U1-SENSE2)") (class "Default")
      (node (ref "R20") (pin "2") (pinfunction "2_2") (pintype "passive"))
      (node (ref "U1") (pin "27") (pinfunction "SENSE2_27") (pintype "passive"))
    )
    (net (code "99") (name "Net-(U1-SLEEP)") (class "Default")
      (node (ref "R6") (pin "1") (pinfunction "1_1") (pintype "passive"))
      (node (ref "U1") (pin "14") (pinfunction "SLEEP_14") (pintype "passive"))
    )
    (net (code "100") (name "Net-(U1-VCP)") (class "Default")
      (node (ref "C13") (pin "1") (pinfunction "1_1") (pintype "passive"))
      (node (ref "U1") (pin "6") (pinfunction "VCP_6") (pintype "passive"))
    )
    (net (code "101") (name "Net-(U1-VREG)") (class "Default")
      (node (ref "C15") (pin "2") (pinfunction "2_2") (pintype "passive"))
      (node (ref "U1") (pin "8") (pinfunction "VREG_8") (pintype "passive"))
    )
    (net (code "102") (name "Net-(U2-CP1)") (class "Default")
      (node (ref "C2") (pin "1") (pinfunction "1_1") (pintype "passive"))
      (node (ref "U2") (pin "4") (pinfunction "CP1_4") (pintype "passive"))
    )
    (net (code "103") (name "Net-(U2-CP2)") (class "Default")
      (node (ref "C2") (pin "2") (pinfunction "2_2") (pintype "passive"))
      (node (ref "U2") (pin "5") (pinfunction "CP2_5") (pintype "passive"))
    )
    (net (code "104") (name "Net-(U2-MS1)") (class "Default")
      (node (ref "R29") (pin "2") (pinfunction "2_2") (pintype "passive"))
      (node (ref "R7") (pin "1") (pinfunction "1_1") (pintype "passive"))
      (node (ref "U2") (pin "9") (pinfunction "MS1_9") (pintype "input"))
    )
    (net (code "105") (name "Net-(U2-MS2)") (class "Default")
      (node (ref "R8") (pin "1") (pinfunction "1_1") (pintype "passive"))
      (node (ref "U2") (pin "10") (pinfunction "MS2_10") (pintype "input"))
    )
    (net (code "106") (name "Net-(U2-MS3)") (class "Default")
      (node (ref "R9") (pin "1") (pinfunction "1_1") (pintype "passive"))
      (node (ref "U2") (pin "11") (pinfunction "MS3_11") (pintype "input"))
    )
    (net (code "107") (name "Net-(U2-ROSC)") (class "Default")
      (node (ref "R27") (pin "2") (pinfunction "2_2") (pintype "passive"))
      (node (ref "U2") (pin "13") (pinfunction "ROSC_13") (pintype "passive"))
    )
    (net (code "108") (name "Net-(U2-SENSE1)") (class "Default")
      (node (ref "R23") (pin "2") (pinfunction "2_2") (pintype "passive"))
      (node (ref "U2") (pin "23") (pinfunction "SENSE1_23") (pintype "passive"))
    )
    (net (code "109") (name "Net-(U2-SENSE2)") (class "Default")
      (node (ref "R22") (pin "2") (pinfunction "2_2") (pintype "passive"))
      (node (ref "U2") (pin "27") (pinfunction "SENSE2_27") (pintype "passive"))
    )
    (net (code "110") (name "Net-(U2-SLEEP)") (class "Default")
      (node (ref "R12") (pin "1") (pinfunction "1_1") (pintype "passive"))
      (node (ref "U2") (pin "14") (pinfunction "SLEEP_14") (pintype "passive"))
    )
    (net (code "111") (name "Net-(U2-VCP)") (class "Default")
      (node (ref "C14") (pin "1") (pinfunction "1_1") (pintype "passive"))
      (node (ref "U2") (pin "6") (pinfunction "VCP_6") (pintype "passive"))
    )
    (net (code "112") (name "Net-(U2-VREG)") (class "Default")
      (node (ref "C16") (pin "2") (pinfunction "2_2") (pintype "passive"))
      (node (ref "U2") (pin "8") (pinfunction "VREG_8") (pintype "passive"))
    )
    (net (code "113") (name "Net-(U3-CP1)") (class "Default")
      (node (ref "C19") (pin "2") (pinfunction "2_2") (pintype "passive"))
      (node (ref "U3") (pin "4") (pinfunction "CP1_4") (pintype "passive"))
    )
    (net (code "114") (name "Net-(U3-CP2)") (class "Default")
      (node (ref "C19") (pin "1") (pinfunction "1_1") (pintype "passive"))
      (node (ref "U3") (pin "5") (pinfunction "CP2_5") (pintype "passive"))
    )
    (net (code "115") (name "Net-(U3-MS1)") (class "Default")
      (node (ref "R30") (pin "1") (pinfunction "1_1") (pintype "passive"))
      (node (ref "R56") (pin "2") (pinfunction "2_2") (pintype "passive"))
      (node (ref "U3") (pin "9") (pinfunction "MS1_9") (pintype "input"))
    )
    (net (code "116") (name "Net-(U3-MS2)") (class "Default")
      (node (ref "R31") (pin "1") (pinfunction "1_1") (pintype "passive"))
      (node (ref "U3") (pin "10") (pinfunction "MS2_10") (pintype "input"))
    )
    (net (code "117") (name "Net-(U3-MS3)") (class "Default")
      (node (ref "R32") (pin "1") (pinfunction "1_1") (pintype "passive"))
      (node (ref "U3") (pin "11") (pinfunction "MS3_11") (pintype "input"))
    )
    (net (code "118") (name "Net-(U3-ROSC)") (class "Default")
      (node (ref "R55") (pin "2") (pinfunction "2_2") (pintype "passive"))
      (node (ref "U3") (pin "13") (pinfunction "ROSC_13") (pintype "passive"))
    )
    (net (code "119") (name "Net-(U3-SENSE1)") (class "Default")
      (node (ref "R50") (pin "2") (pinfunction "2_2") (pintype "passive"))
      (node (ref "U3") (pin "23") (pinfunction "SENSE1_23") (pintype "passive"))
    )
    (net (code "120") (name "Net-(U3-SENSE2)") (class "Default")
      (node (ref "R49") (pin "2") (pinfunction "2_2") (pintype "passive"))
      (node (ref "U3") (pin "27") (pinfunction "SENSE2_27") (pintype "passive"))
    )
    (net (code "121") (name "Net-(U3-SLEEP)") (class "Default")
      (node (ref "R35") (pin "1") (pinfunction "1_1") (pintype "passive"))
      (node (ref "U3") (pin "14") (pinfunction "SLEEP_14") (pintype "passive"))
    )
    (net (code "122") (name "Net-(U3-VCP)") (class "Default")
      (node (ref "C30") (pin "1") (pinfunction "1_1") (pintype "passive"))
      (node (ref "U3") (pin "6") (pinfunction "VCP_6") (pintype "passive"))
    )
    (net (code "123") (name "Net-(U3-VREG)") (class "Default")
      (node (ref "C33") (pin "2") (pinfunction "2_2") (pintype "passive"))
      (node (ref "U3") (pin "8") (pinfunction "VREG_8") (pintype "passive"))
    )
    (net (code "124") (name "Net-(U4-CP1)") (class "Default")
      (node (ref "C20") (pin "1") (pinfunction "1_1") (pintype "passive"))
      (node (ref "U4") (pin "4") (pinfunction "CP1_4") (pintype "passive"))
    )
    (net (code "125") (name "Net-(U4-CP2)") (class "Default")
      (node (ref "C20") (pin "2") (pinfunction "2_2") (pintype "passive"))
      (node (ref "U4") (pin "5") (pinfunction "CP2_5") (pintype "passive"))
    )
    (net (code "126") (name "Net-(U4-MS1)") (class "Default")
      (node (ref "R36") (pin "1") (pinfunction "1_1") (pintype "passive"))
      (node (ref "R58") (pin "2") (pinfunction "2_2") (pintype "passive"))
      (node (ref "U4") (pin "9") (pinfunction "MS1_9") (pintype "input"))
    )
    (net (code "127") (name "Net-(U4-MS2)") (class "Default")
      (node (ref "R37") (pin "1") (pinfunction "1_1") (pintype "passive"))
      (node (ref "U4") (pin "10") (pinfunction "MS2_10") (pintype "input"))
    )
    (net (code "128") (name "Net-(U4-MS3)") (class "Default")
      (node (ref "R38") (pin "1") (pinfunction "1_1") (pintype "passive"))
      (node (ref "U4") (pin "11") (pinfunction "MS3_11") (pintype "input"))
    )
    (net (code "129") (name "Net-(U4-ROSC)") (class "Default")
      (node (ref "R57") (pin "2") (pinfunction "2_2") (pintype "passive"))
      (node (ref "U4") (pin "13") (pinfunction "ROSC_13") (pintype "passive"))
    )
    (net (code "130") (name "Net-(U4-SENSE1)") (class "Default")
      (node (ref "R52") (pin "2") (pinfunction "2_2") (pintype "passive"))
      (node (ref "U4") (pin "23") (pinfunction "SENSE1_23") (pintype "passive"))
    )
    (net (code "131") (name "Net-(U4-SENSE2)") (class "Default")
      (node (ref "R51") (pin "2") (pinfunction "2_2") (pintype "passive"))
      (node (ref "U4") (pin "27") (pinfunction "SENSE2_27") (pintype "passive"))
    )
    (net (code "132") (name "Net-(U4-SLEEP)") (class "Default")
      (node (ref "R41") (pin "1") (pinfunction "1_1") (pintype "passive"))
      (node (ref "U4") (pin "14") (pinfunction "SLEEP_14") (pintype "passive"))
    )
    (net (code "133") (name "Net-(U4-VCP)") (class "Default")
      (node (ref "C32") (pin "1") (pinfunction "1_1") (pintype "passive"))
      (node (ref "U4") (pin "6") (pinfunction "VCP_6") (pintype "passive"))
    )
    (net (code "134") (name "Net-(U4-VREG)") (class "Default")
      (node (ref "C34") (pin "2") (pinfunction "2_2") (pintype "passive"))
      (node (ref "U4") (pin "8") (pinfunction "VREG_8") (pintype "passive"))
    )
    (net (code "135") (name "Net-(U7-A)") (class "Default")
      (node (ref "R14") (pin "1") (pinfunction "1_1") (pintype "passive"))
      (node (ref "U7") (pin "1") (pinfunction "A_1") (pintype "passive"))
    )
    (net (code "136") (name "V3.3") (class "Default")
      (node (ref "C21") (pin "2") (pinfunction "2_2") (pintype "passive"))
      (node (ref "C22") (pin "2") (pinfunction "2_2") (pintype "passive"))
      (node (ref "C23") (pin "2") (pinfunction "2_2") (pintype "passive"))
      (node (ref "C24") (pin "2") (pinfunction "2_2") (pintype "passive"))
      (node (ref "C3") (pin "2") (pinfunction "2_2") (pintype "passive"))
      (node (ref "C4") (pin "2") (pinfunction "2_2") (pintype "passive"))
      (node (ref "C5") (pin "2") (pinfunction "2_2") (pintype "passive"))
      (node (ref "C6") (pin "2") (pinfunction "2_2") (pintype "passive"))
      (node (ref "D2") (pin "2") (pinfunction "A_2") (pintype "passive"))
      (node (ref "D3") (pin "2") (pinfunction "A_2") (pintype "passive"))
      (node (ref "D5") (pin "2") (pinfunction "A_2") (pintype "passive"))
      (node (ref "D6") (pin "2") (pinfunction "A_2") (pintype "passive"))
      (node (ref "J12") (pin "1") (pinfunction "1_1") (pintype "passive"))
      (node (ref "J13") (pin "1") (pinfunction "1_1") (pintype "passive"))
      (node (ref "J14") (pin "1") (pinfunction "1_1") (pintype "passive"))
      (node (ref "J15") (pin "1") (pinfunction "1_1") (pintype "passive"))
      (node (ref "R1") (pin "2") (pinfunction "2_2") (pintype "passive"))
      (node (ref "R12") (pin "2") (pinfunction "2_2") (pintype "passive"))
      (node (ref "R13") (pin "2") (pinfunction "2_2") (pintype "passive"))
      (node (ref "R18") (pin "2") (pinfunction "2_2") (pintype "passive"))
      (node (ref "R19") (pin "2") (pinfunction "2_2") (pintype "passive"))
      (node (ref "R2") (pin "2") (pinfunction "2_2") (pintype "passive"))
      (node (ref "R3") (pin "2") (pinfunction "2_2") (pintype "passive"))
      (node (ref "R30") (pin "2") (pinfunction "2_2") (pintype "passive"))
      (node (ref "R31") (pin "2") (pinfunction "2_2") (pintype "passive"))
      (node (ref "R32") (pin "2") (pinfunction "2_2") (pintype "passive"))
      (node (ref "R35") (pin "2") (pinfunction "2_2") (pintype "passive"))
      (node (ref "R36") (pin "2") (pinfunction "2_2") (pintype "passive"))
      (node (ref "R37") (pin "2") (pinfunction "2_2") (pintype "passive"))
      (node (ref "R38") (pin "2") (pinfunction "2_2") (pintype "passive"))
      (node (ref "R41") (pin "2") (pinfunction "2_2") (pintype "passive"))
      (node (ref "R42") (pin "2") (pinfunction "2_2") (pintype "passive"))
      (node (ref "R45") (pin "2") (pinfunction "2_2") (pintype "passive"))
      (node (ref "R47") (pin "2") (pinfunction "2_2") (pintype "passive"))
      (node (ref "R48") (pin "2") (pinfunction "2_2") (pintype "passive"))
      (node (ref "R6") (pin "2") (pinfunction "2_2") (pintype "passive"))
      (node (ref "R7") (pin "2") (pinfunction "2_2") (pintype "passive"))
      (node (ref "R8") (pin "2") (pinfunction "2_2") (pintype "passive"))
      (node (ref "R9") (pin "2") (pinfunction "2_2") (pintype "passive"))
      (node (ref "U1") (pin "15") (pinfunction "VDD_15") (pintype "passive"))
      (node (ref "U2") (pin "15") (pinfunction "VDD_15") (pintype "passive"))
      (node (ref "U3") (pin "15") (pinfunction "VDD_15") (pintype "passive"))
      (node (ref "U4") (pin "15") (pinfunction "VDD_15") (pintype "passive"))
    )
    (net (code "137") (name "V5") (class "Default")
      (node (ref "J17") (pin "2") (pinfunction "2_2") (pintype "passive"))
      (node (ref "J3") (pin "1") (pinfunction "1_1") (pintype "passive"))
      (node (ref "J3") (pin "2") (pinfunction "2_2") (pintype "passive"))
      (node (ref "J6") (pin "1") (pinfunction "1_1") (pintype "passive"))
      (node (ref "J6") (pin "2") (pinfunction "2_2") (pintype "passive"))
      (node (ref "J9") (pin "1") (pinfunction "1_1") (pintype "passive"))
      (node (ref "J9") (pin "2") (pinfunction "2_2") (pintype "passive"))
    )
    (net (code "138") (name "VA3.3") (class "Default")
      (node (ref "R59") (pin "2") (pinfunction "2_2") (pintype "passive"))
      (node (ref "R60") (pin "2") (pinfunction "2_2") (pintype "passive"))
    )
    (net (code "139") (name "VMM") (class "Default")
      (node (ref "C10") (pin "2") (pinfunction "2_2") (pintype "passive"))
      (node (ref "C11") (pin "1") (pinfunction "1_1") (pintype "passive"))
      (node (ref "C12") (pin "1") (pinfunction "1_1") (pintype "passive"))
      (node (ref "C13") (pin "2") (pinfunction "2_2") (pintype "passive"))
      (node (ref "C14") (pin "2") (pinfunction "2_2") (pintype "passive"))
      (node (ref "C25") (pin "2") (pinfunction "2_2") (pintype "passive"))
      (node (ref "C26") (pin "2") (pinfunction "2_2") (pintype "passive"))
      (node (ref "C27") (pin "1") (pinfunction "1_1") (pintype "passive"))
      (node (ref "C28") (pin "2") (pinfunction "2_2") (pintype "passive"))
      (node (ref "C29") (pin "2") (pinfunction "2_2") (pintype "passive"))
      (node (ref "C30") (pin "2") (pinfunction "2_2") (pintype "passive"))
      (node (ref "C31") (pin "1") (pinfunction "1_1") (pintype "passive"))
      (node (ref "C32") (pin "2") (pinfunction "2_2") (pintype "passive"))
      (node (ref "C62") (pin "2") (pinfunction "2_2") (pintype "passive"))
      (node (ref "C7") (pin "1") (pinfunction "1_1") (pintype "passive"))
      (node (ref "C8") (pin "2") (pinfunction "2_2") (pintype "passive"))
      (node (ref "C9") (pin "2") (pinfunction "2_2") (pintype "passive"))
      (node (ref "D15") (pin "1") (pinfunction "K_1") (pintype "passive"))
      (node (ref "D16") (pin "1") (pinfunction "K_1") (pintype "passive"))
      (node (ref "J21") (pin "1") (pinfunction "1_1") (pintype "passive"))
      (node (ref "J7") (pin "3") (pinfunction "3_3") (pintype "passive"))
      (node (ref "J8") (pin "3") (pinfunction "3_3") (pintype "passive"))
      (node (ref "R106") (pin "2") (pinfunction "2_2") (pintype "passive"))
      (node (ref "R43") (pin "2") (pinfunction "2_2") (pintype "passive"))
      (node (ref "R66") (pin "2") (pinfunction "2_2") (pintype "passive"))
      (node (ref "R67") (pin "2") (pinfunction "2_2") (pintype "passive"))
      (node (ref "U1") (pin "22") (pinfunction "VBB1_22") (pintype "passive"))
      (node (ref "U1") (pin "28") (pinfunction "VBB2_28") (pintype "passive"))
      (node (ref "U2") (pin "22") (pinfunction "VBB1_22") (pintype "passive"))
      (node (ref "U2") (pin "28") (pinfunction "VBB2_28") (pintype "passive"))
      (node (ref "U3") (pin "22") (pinfunction "VBB1_22") (pintype "passive"))
      (node (ref "U3") (pin "28") (pinfunction "VBB2_28") (pintype "passive"))
      (node (ref "U4") (pin "22") (pinfunction "VBB1_22") (pintype "passive"))
      (node (ref "U4") (pin "28") (pinfunction "VBB2_28") (pintype "passive"))
    )
    (net (code "140") (name "unconnected-(U1-NC-Pad7)") (class "Default")
      (node (ref "U1") (pin "7") (pinfunction "NC_7") (pintype "passive+no_connect"))
    )
    (net (code "141") (name "unconnected-(U1-NC-Pad20)") (class "Default")
      (node (ref "U1") (pin "20") (pinfunction "NC_20") (pintype "passive+no_connect"))
    )
    (net (code "142") (name "unconnected-(U1-NC-Pad25)") (class "Default")
      (node (ref "U1") (pin "25") (pinfunction "NC_25") (pintype "passive+no_connect"))
    )
    (net (code "143") (name "unconnected-(U2-NC-Pad7)") (class "Default")
      (node (ref "U2") (pin "7") (pinfunction "NC_7") (pintype "passive+no_connect"))
    )
    (net (code "144") (name "unconnected-(U2-NC-Pad20)") (class "Default")
      (node (ref "U2") (pin "20") (pinfunction "NC_20") (pintype "passive+no_connect"))
    )
    (net (code "145") (name "unconnected-(U2-NC-Pad25)") (class "Default")
      (node (ref "U2") (pin "25") (pinfunction "NC_25") (pintype "passive+no_connect"))
    )
    (net (code "146") (name "unconnected-(U3-NC-Pad7)") (class "Default")
      (node (ref "U3") (pin "7") (pinfunction "NC_7") (pintype "passive+no_connect"))
    )
    (net (code "147") (name "unconnected-(U3-NC-Pad20)") (class "Default")
      (node (ref "U3") (pin "20") (pinfunction "NC_20") (pintype "passive+no_connect"))
    )
    (net (code "148") (name "unconnected-(U3-NC-Pad25)") (class "Default")
      (node (ref "U3") (pin "25") (pinfunction "NC_25") (pintype "passive+no_connect"))
    )
    (net (code "149") (name "unconnected-(U4-NC-Pad7)") (class "Default")
      (node (ref "U4") (pin "7") (pinfunction "NC_7") (pintype "passive+no_connect"))
    )
    (net (code "150") (name "unconnected-(U4-NC-Pad20)") (class "Default")
      (node (ref "U4") (pin "20") (pinfunction "NC_20") (pintype "passive+no_connect"))
    )
    (net (code "151") (name "unconnected-(U4-NC-Pad25)") (class "Default")
      (node (ref "U4") (pin "25") (pinfunction "NC_25") (pintype "passive+no_connect"))
    )
  )
)
